# MindPX_V2_8_SCH.net
KiCad netlist of a schematic drawn in Altium Designer
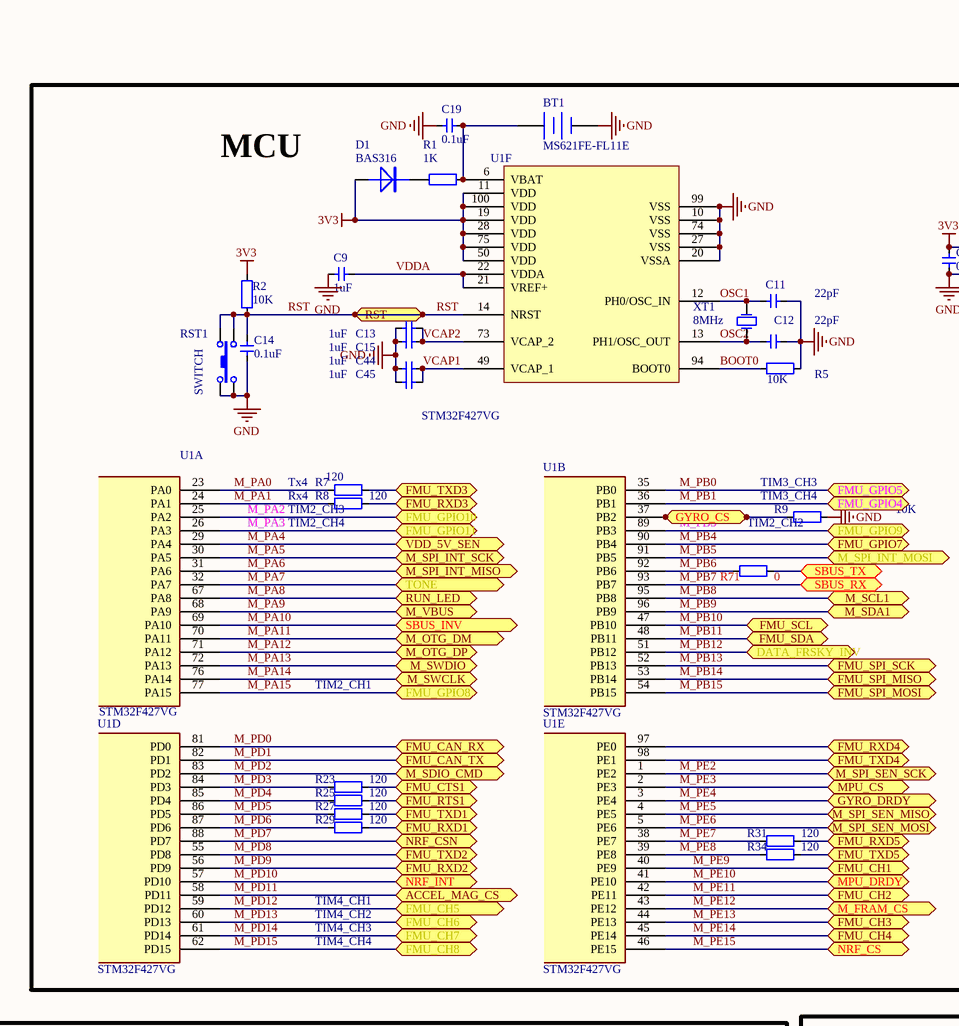
[diagram p0: MindPX V2.8 SCH.SchDoc, top left]
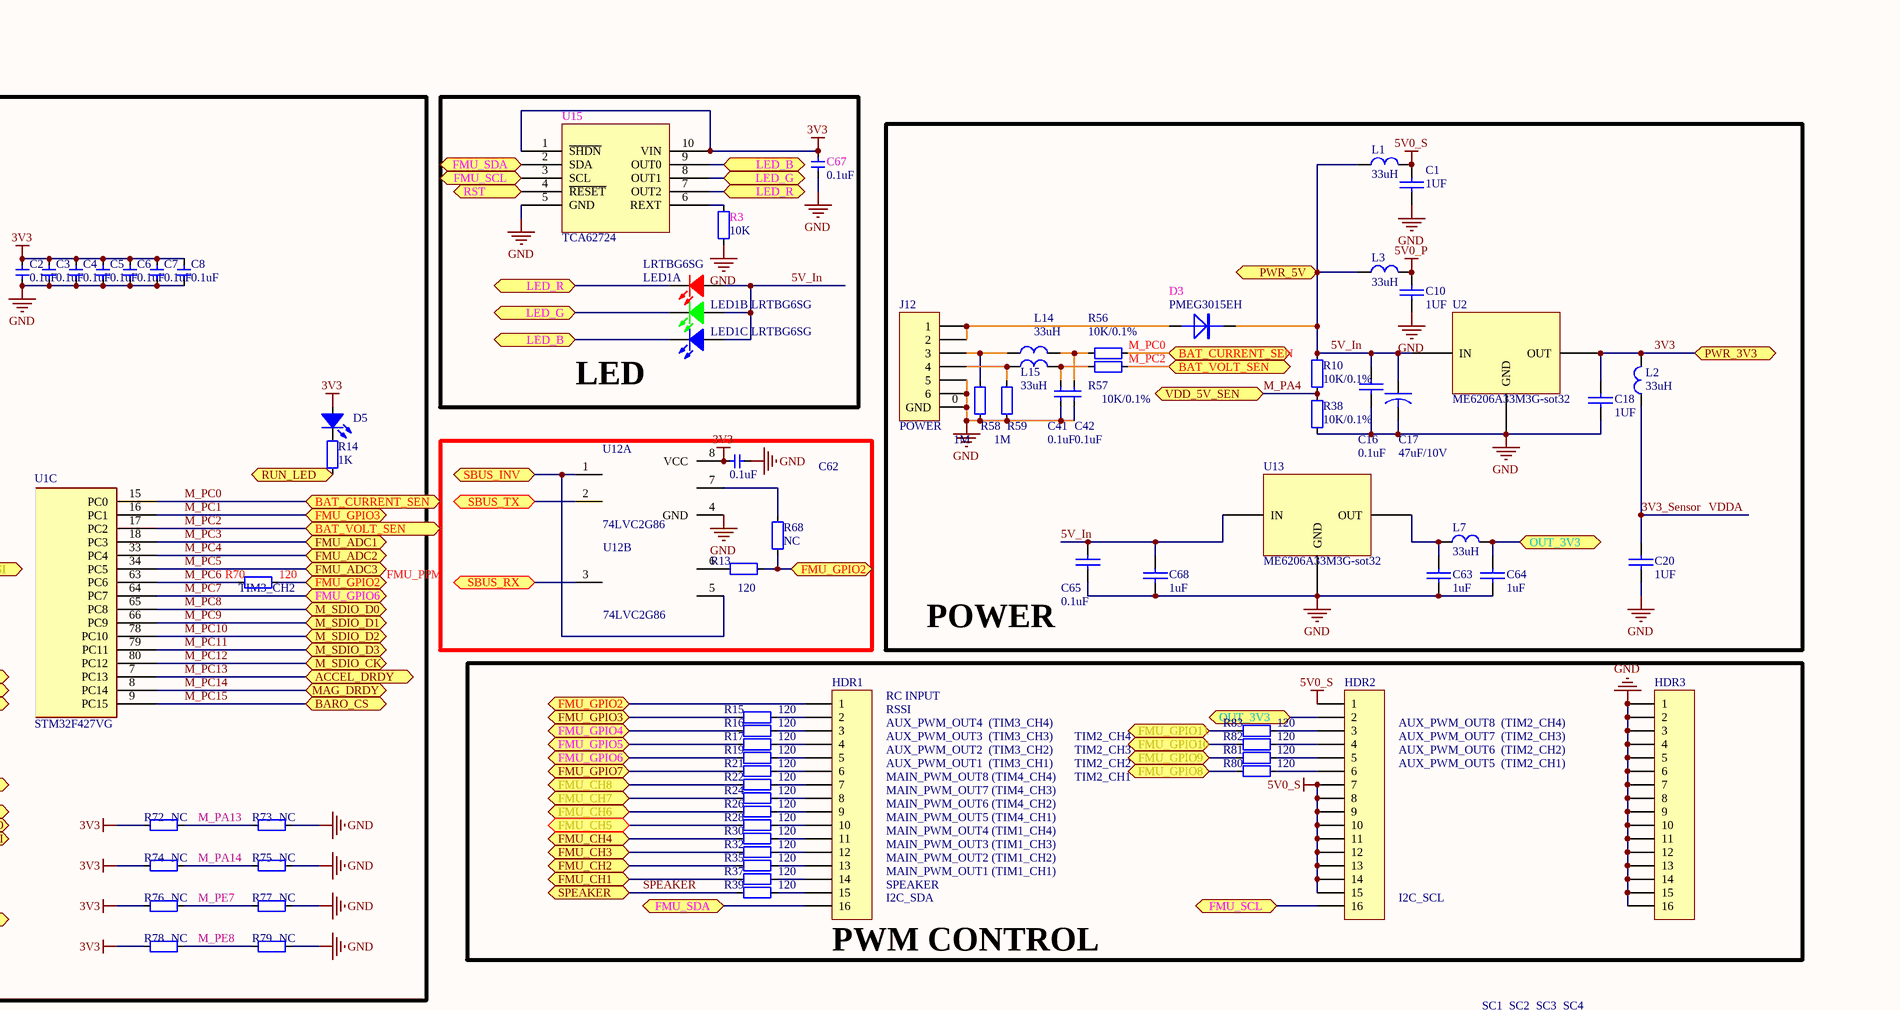
[diagram p1: MindPX V2.8 SCH.SchDoc, top right]
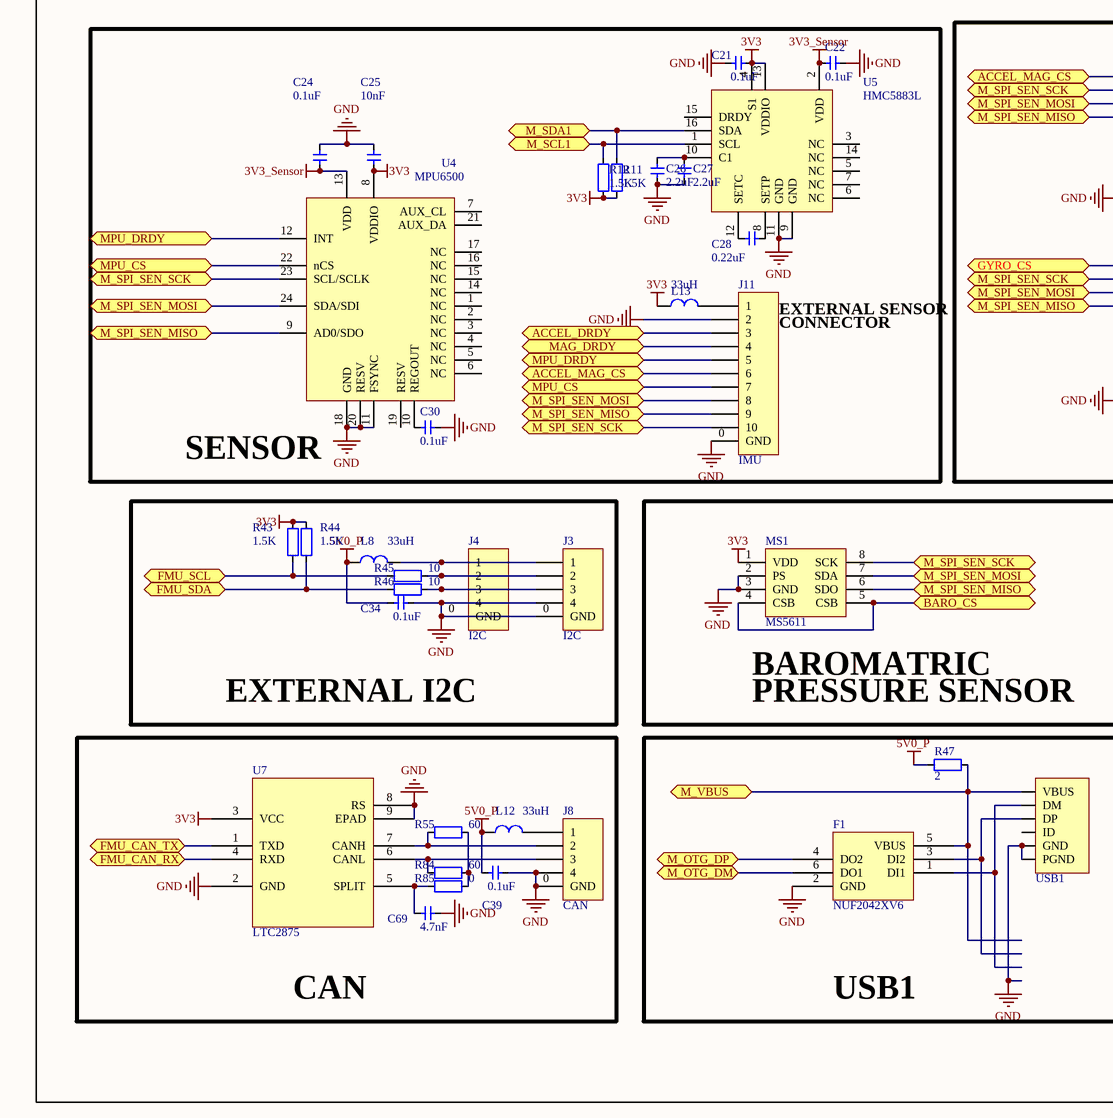
[diagram p2: MindPX V2.8 SCH.SchDoc, bottom left]
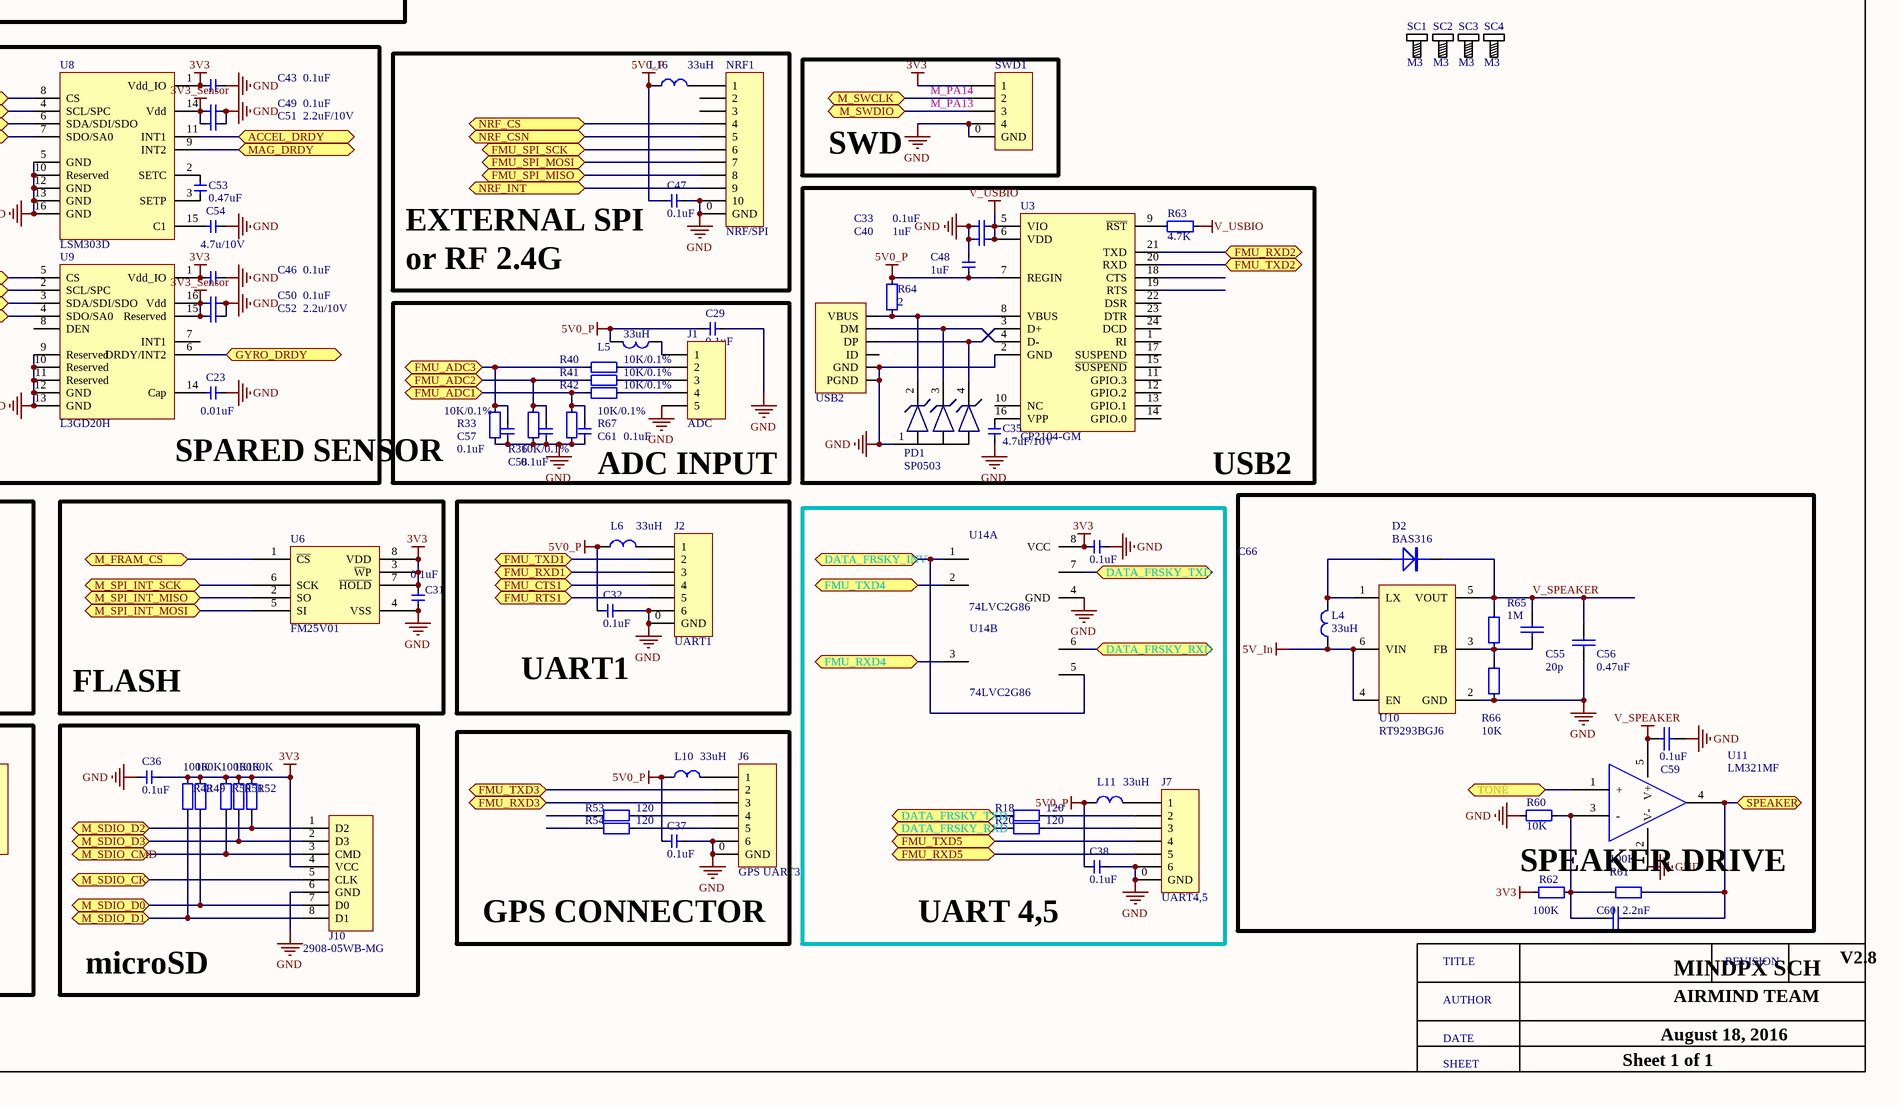
[diagram p3: MindPX V2.8 SCH.SchDoc, bottom right]

(export (version "E")
  (design (tool "Eeschema 10.0.6"))
  (components
    (comp (ref "BT1")
      (value "MS621FE-FL11E")
      (footprint "MS621FE")
      (description "Multicell Battery")
      (fields (field (name "PUBLISHER") "Altium Limited"))
      (libsource (lib "Miscellaneous Devices") (part "Battery"))
    )
    (comp (ref "C1")
      (value "1UF")
      (footprint "C0603")
      (description "Capacitor")
      (libsource (lib "*") (part "CAP"))
    )
    (comp (ref "C2")
      (value "0.1uF")
      (footprint "C0603")
      (description "Capacitor")
      (libsource (lib "SCH_Passive") (part "Cap_0603"))
    )
    (comp (ref "C3")
      (value "0.1uF")
      (footprint "C0603")
      (description "Capacitor")
      (libsource (lib "SCH_Passive") (part "Cap_0603"))
    )
    (comp (ref "C4")
      (value "0.1uF")
      (footprint "C0603")
      (description "Capacitor")
      (libsource (lib "SCH_Passive") (part "Cap_0603"))
    )
    (comp (ref "C5")
      (value "0.1uF")
      (footprint "C0603")
      (description "Capacitor")
      (libsource (lib "SCH_Passive") (part "Cap_0603"))
    )
    (comp (ref "C6")
      (value "0.1uF")
      (footprint "C0603")
      (description "Capacitor")
      (libsource (lib "SCH_Passive") (part "Cap_0603"))
    )
    (comp (ref "C7")
      (value "0.1uF")
      (footprint "C0603")
      (description "Capacitor")
      (libsource (lib "SCH_Passive") (part "Cap_0603"))
    )
    (comp (ref "C8")
      (value "0.1uF")
      (footprint "C0603")
      (description "Capacitor")
      (libsource (lib "SCH_Passive") (part "Cap_0603"))
    )
    (comp (ref "C9")
      (value "1uF")
      (footprint "C0603")
      (description "Capacitor")
      (libsource (lib "SCH_Passive") (part "Cap_0603"))
    )
    (comp (ref "C10")
      (value "1UF")
      (footprint "C0603")
      (description "Capacitor")
      (libsource (lib "*") (part "CAP"))
    )
    (comp (ref "C11")
      (value "22pF")
      (footprint "C0603")
      (description "Capacitor")
      (libsource (lib "SCH_Passive") (part "Cap_0603"))
    )
    (comp (ref "C12")
      (value "22pF")
      (footprint "C0603")
      (description "Capacitor")
      (libsource (lib "SCH_Passive") (part "Cap_0603"))
    )
    (comp (ref "C13")
      (value "1uF")
      (footprint "C0603")
      (description "Capacitor")
      (libsource (lib "SCH_Passive") (part "Cap_0603"))
    )
    (comp (ref "C14")
      (value "0.1uF")
      (footprint "C0603")
      (description "Capacitor")
      (libsource (lib "SCH_Passive") (part "Cap_0603"))
    )
    (comp (ref "C15")
      (value "1uF")
      (footprint "C0603")
      (description "Capacitor")
      (libsource (lib "SCH_Passive") (part "Cap_0603"))
    )
    (comp (ref "C16")
      (value "0.1uF")
      (footprint "C0603")
      (description "Capacitor")
      (libsource (lib "*") (part "CAP"))
    )
    (comp (ref "C17")
      (value "47uF/10V")
      (footprint "钽电容")
      (description "Capacitor")
      (libsource (lib "*") (part "CAPACITOR"))
    )
    (comp (ref "C18")
      (value "1UF")
      (footprint "C0603")
      (description "Capacitor")
      (libsource (lib "*") (part "CAP"))
    )
    (comp (ref "C19")
      (value "0.1uF")
      (footprint "C0603")
      (description "Capacitor")
      (libsource (lib "SCH_Passive") (part "Cap_0603"))
    )
    (comp (ref "C20")
      (value "1UF")
      (footprint "C0603")
      (description "Capacitor")
      (libsource (lib "*") (part "CAP"))
    )
    (comp (ref "C21")
      (value "0.1uF")
      (footprint "C0603")
      (description "Capacitor")
      (libsource (lib "SCH_Passive") (part "Cap_0603"))
    )
    (comp (ref "C22")
      (value "0.1uF")
      (footprint "C0603")
      (description "Capacitor")
      (libsource (lib "SCH_Passive") (part "Cap_0603"))
    )
    (comp (ref "C23")
      (value "0.01uF")
      (footprint "C0603")
      (description "Capacitor")
      (libsource (lib "SCH_Passive") (part "Cap_0603"))
    )
    (comp (ref "C24")
      (value "0.1uF")
      (footprint "C0603")
      (description "Capacitor")
      (libsource (lib "SCH_Passive") (part "Cap_0603"))
    )
    (comp (ref "C25")
      (value "10nF")
      (footprint "C0603")
      (description "Capacitor")
      (libsource (lib "SCH_Passive") (part "Cap_0603"))
    )
    (comp (ref "C26")
      (value "2.2uF")
      (footprint "C0603")
      (description "Capacitor")
      (libsource (lib "SCH_Passive") (part "Cap_0603"))
    )
    (comp (ref "C27")
      (value "2.2uF")
      (footprint "C0603")
      (description "Capacitor")
      (libsource (lib "SCH_Passive") (part "Cap_0603"))
    )
    (comp (ref "C28")
      (value "0.22uF")
      (footprint "C0603")
      (description "Capacitor")
      (libsource (lib "SCH_Passive") (part "Cap_0603"))
    )
    (comp (ref "C29")
      (value "0.1uF")
      (footprint "C0603")
      (description "Capacitor")
      (libsource (lib "SCH_Passive") (part "Cap_0603"))
    )
    (comp (ref "C30")
      (value "0.1uF")
      (footprint "C0603")
      (description "Capacitor")
      (libsource (lib "SCH_Passive") (part "Cap_0603"))
    )
    (comp (ref "C31")
      (value "0.1uF")
      (footprint "C0603")
      (description "Capacitor")
      (libsource (lib "SCH_Passive") (part "Cap_0603"))
    )
    (comp (ref "C32")
      (value "0.1uF")
      (footprint "C0603")
      (description "Capacitor")
      (libsource (lib "SCH_Passive") (part "Cap_0603"))
    )
    (comp (ref "C33")
      (value "0.1uF")
      (footprint "C0603")
      (description "Capacitor")
      (libsource (lib "SCH_Passive") (part "Cap_0603"))
    )
    (comp (ref "C34")
      (value "0.1uF")
      (footprint "C0603")
      (description "Capacitor")
      (libsource (lib "SCH_Passive") (part "Cap_0603"))
    )
    (comp (ref "C35")
      (value "4.7uF/10V")
      (footprint "C0603")
      (description "Capacitor")
      (libsource (lib "SCH_Passive") (part "Cap_0603"))
    )
    (comp (ref "C36")
      (value "0.1uF")
      (footprint "C0603")
      (description "Capacitor")
      (libsource (lib "SCH_Passive") (part "Cap_0603"))
    )
    (comp (ref "C37")
      (value "0.1uF")
      (footprint "C0603")
      (description "Capacitor")
      (libsource (lib "SCH_Passive") (part "Cap_0603"))
    )
    (comp (ref "C38")
      (value "0.1uF")
      (footprint "C0603")
      (description "Capacitor")
      (libsource (lib "SCH_Passive") (part "Cap_0603"))
    )
    (comp (ref "C39")
      (value "0.1uF")
      (footprint "C0603")
      (description "Capacitor")
      (libsource (lib "SCH_Passive") (part "Cap_0603"))
    )
    (comp (ref "C40")
      (value "1uF")
      (footprint "C0603")
      (description "Capacitor")
      (libsource (lib "SCH_Passive") (part "Cap_0603"))
    )
    (comp (ref "C41")
      (value "0.1uF")
      (footprint "C0603")
      (description "Capacitor")
      (libsource (lib "") (part "Cap_0603_1"))
    )
    (comp (ref "C42")
      (value "0.1uF")
      (footprint "C0603")
      (description "Capacitor")
      (libsource (lib "") (part "Cap_0603_1"))
    )
    (comp (ref "C43")
      (value "0.1uF")
      (footprint "C0603")
      (description "Capacitor")
      (libsource (lib "SCH_Passive") (part "Cap_0603"))
    )
    (comp (ref "C44")
      (value "1uF")
      (footprint "C0603")
      (description "Capacitor")
      (libsource (lib "SCH_Passive") (part "Cap_0603"))
    )
    (comp (ref "C45")
      (value "1uF")
      (footprint "C0603")
      (description "Capacitor")
      (libsource (lib "SCH_Passive") (part "Cap_0603"))
    )
    (comp (ref "C46")
      (value "0.1uF")
      (footprint "C0603")
      (description "Capacitor")
      (libsource (lib "SCH_Passive") (part "Cap_0603"))
    )
    (comp (ref "C47")
      (value "0.1uF")
      (footprint "C0603")
      (description "Capacitor")
      (libsource (lib "SCH_Passive") (part "Cap_0603"))
    )
    (comp (ref "C48")
      (value "1uF")
      (footprint "C0603")
      (description "Capacitor")
      (libsource (lib "SCH_Passive") (part "Cap_0603"))
    )
    (comp (ref "C49")
      (value "0.1uF")
      (footprint "C0603")
      (description "Capacitor")
      (libsource (lib "SCH_Passive") (part "Cap_0603"))
    )
    (comp (ref "C50")
      (value "0.1uF")
      (footprint "C0603")
      (description "Capacitor")
      (libsource (lib "SCH_Passive") (part "Cap_0603"))
    )
    (comp (ref "C51")
      (value "2.2uF/10V")
      (footprint "C0603")
      (description "Capacitor")
      (libsource (lib "SCH_Passive") (part "Cap_0603"))
    )
    (comp (ref "C52")
      (value "2.2u/10V")
      (footprint "C0603")
      (description "Capacitor")
      (libsource (lib "SCH_Passive") (part "Cap_0603"))
    )
    (comp (ref "C53")
      (value "0.47uF")
      (footprint "C0603")
      (description "Capacitor")
      (libsource (lib "SCH_Passive") (part "Cap_0603"))
    )
    (comp (ref "C54")
      (value "4.7u/10V")
      (footprint "C0603")
      (description "Capacitor")
      (libsource (lib "SCH_Passive") (part "Cap_0603"))
    )
    (comp (ref "C55")
      (value "20p")
      (footprint "C0603")
      (description "Capacitor")
      (libsource (lib "*") (part "CAP"))
    )
    (comp (ref "C56")
      (value "0.47uF")
      (footprint "C0805")
      (description "Capacitor")
      (libsource (lib "*") (part "CAP"))
    )
    (comp (ref "C57")
      (value "0.1uF")
      (footprint "C0603")
      (description "Capacitor")
      (libsource (lib "SCH_Passive") (part "Cap_0603"))
    )
    (comp (ref "C58")
      (value "0.1uF")
      (footprint "C0603")
      (description "Capacitor")
      (libsource (lib "SCH_Passive") (part "Cap_0603"))
    )
    (comp (ref "C59")
      (value "0.1uF")
      (footprint "C0603")
      (description "Capacitor")
      (libsource (lib "*") (part "CAP"))
    )
    (comp (ref "C60")
      (value "2.2nF")
      (footprint "C0603")
      (description "Capacitor")
      (libsource (lib "*") (part "CAP"))
    )
    (comp (ref "C61")
      (value "0.1uF")
      (footprint "C0603")
      (description "Capacitor")
      (libsource (lib "SCH_Passive") (part "Cap_0603"))
    )
    (comp (ref "C62")
      (value "0.1uF")
      (footprint "C0603")
      (description "Capacitor")
      (libsource (lib "SCH_Passive") (part "Cap_0603"))
    )
    (comp (ref "C63")
      (value "1uF")
      (footprint "C0603")
      (description "Capacitor")
      (libsource (lib "*") (part "CAP"))
    )
    (comp (ref "C64")
      (value "1uF")
      (footprint "C0603")
      (description "Capacitor")
      (libsource (lib "*") (part "CAP"))
    )
    (comp (ref "C65")
      (value "0.1uF")
      (footprint "C0603")
      (description "Capacitor")
      (libsource (lib "*") (part "CAP"))
    )
    (comp (ref "C66")
      (value "0.1uF")
      (footprint "C0603")
      (description "Capacitor")
      (libsource (lib "SCH_Passive") (part "Cap_0603"))
    )
    (comp (ref "C67")
      (value "0.1uF")
      (footprint "C0603")
      (description "Capacitor")
      (libsource (lib "") (part "Cap_0603_1"))
    )
    (comp (ref "C68")
      (value "1uF")
      (footprint "C0603")
      (description "Capacitor")
      (libsource (lib "*") (part "CAP"))
    )
    (comp (ref "C69")
      (value "4.7nF")
      (footprint "C0603")
      (description "Capacitor")
      (libsource (lib "SCH_Passive") (part "Cap_0603"))
    )
    (comp (ref "D1") (value "BAS316") (footprint "SOD323_AK") (libsource (lib "Zzhsch") (part "DIODE")))
    (comp (ref "D2") (value "BAS316") (footprint "SOD323_AK") (libsource (lib "Zzhsch") (part "DIODE")))
    (comp (ref "D3") (value "PMEG3015EH") (footprint "SOD123/X.85") (libsource (lib "Zzhsch") (part "DIODE")))
    (comp (ref "D5")
      (value "LED_0603")
      (footprint "0603")
      (description "LED")
      (libsource (lib "Zzhsch") (part "LED_0603"))
    )
    (comp (ref "F1")
      (value "NUF2042XV6")
      (footprint "SOT-563-6")
      (libsource (lib "Zzhsch") (part "NUF2042XV6"))
    )
    (comp (ref "HDR1")
      (value "MHDR1X16")
      (footprint "HDR1X16")
      (description "Header, 16-Pin")
      (fields (field (name "PUBLISHER") "Altium Limited"))
      (libsource (lib "Miscellaneous Connectors") (part "MHDR1X16"))
    )
    (comp (ref "HDR2")
      (value "MHDR1X16")
      (footprint "HDR1X16")
      (description "Header, 16-Pin")
      (fields (field (name "PUBLISHER") "Altium Limited"))
      (libsource (lib "Miscellaneous Connectors") (part "MHDR1X16"))
    )
    (comp (ref "HDR3")
      (value "MHDR1X16")
      (footprint "HDR1X16")
      (description "Header, 16-Pin")
      (fields (field (name "PUBLISHER") "Altium Limited"))
      (libsource (lib "Miscellaneous Connectors") (part "MHDR1X16"))
    )
    (comp (ref "J1")
      (value "ADC")
      (footprint "HDR1X5")
      (description "Header, 5-Pin")
      (fields (field (name "PUBLISHER") "Altium Limited"))
      (libsource (lib "Miscellaneous Connectors") (part "Header 5"))
    )
    (comp (ref "J2")
      (value "UART1")
      (footprint "DF13A-6P-1.25H")
      (description "Header, 7-Pin")
      (fields (field (name "PUBLISHER") "Altium Limited"))
      (libsource (lib "Zzhsch") (part "DF13_6"))
    )
    (comp (ref "J3")
      (value "I2C")
      (footprint "DF13A-4P-1.25H")
      (description "Header,4-Pin")
      (fields (field (name "PUBLISHER") "Altium Limited"))
      (libsource (lib "Zzhsch") (part "DF13_4"))
    )
    (comp (ref "J4")
      (value "I2C")
      (footprint "DF13A-4P-1.25H")
      (description "Header,4-Pin")
      (fields (field (name "PUBLISHER") "Altium Limited"))
      (libsource (lib "Zzhsch") (part "DF13_4"))
    )
    (comp (ref "J6")
      (value "GPS UART3")
      (footprint "DF13A-6P-1.25H")
      (description "Header, 7-Pin")
      (fields (field (name "PUBLISHER") "Altium Limited"))
      (libsource (lib "Zzhsch") (part "DF13_6"))
    )
    (comp (ref "J7")
      (value "UART4,5")
      (footprint "DF13A-6P-1.25H")
      (description "Header, 7-Pin")
      (fields (field (name "PUBLISHER") "Altium Limited"))
      (libsource (lib "Zzhsch") (part "DF13_6"))
    )
    (comp (ref "J8")
      (value "CAN")
      (footprint "DF13A-4P-1.25H")
      (description "Header,4-Pin")
      (fields (field (name "PUBLISHER") "Altium Limited"))
      (libsource (lib "Zzhsch") (part "DF13_4"))
    )
    (comp (ref "J10")
      (value "2908-05WB-MG")
      (footprint "SD_Card_TF")
      (description "SD")
      (libsource (lib "Zzhsch") (part "microSD_interface"))
    )
    (comp (ref "J11")
      (value "IMU")
      (footprint "FPC10/0.5")
      (description "Header, 8-Pin")
      (fields (field (name "PUBLISHER") "Altium Limited"))
      (libsource (lib "Zzhsch") (part "DF13_10"))
    )
    (comp (ref "J12")
      (value "POWER")
      (footprint "DF13A-6P-1.25H")
      (description "Header, 7-Pin")
      (fields (field (name "PUBLISHER") "Altium Limited"))
      (libsource (lib "") (part "DF13_6_1"))
    )
    (comp (ref "L1")
      (value "33uH")
      (footprint "L0603")
      (description "Inductor")
      (fields (field (name "PUBLISHER") "Altium Limited"))
      (libsource (lib "Zzhsch") (part "Inductor_smt"))
    )
    (comp (ref "L2")
      (value "33uH")
      (footprint "L0603")
      (description "Inductor")
      (fields (field (name "PUBLISHER") "Altium Limited"))
      (libsource (lib "Zzhsch") (part "Inductor_smt"))
    )
    (comp (ref "L3")
      (value "33uH")
      (footprint "L0603")
      (description "Inductor")
      (fields (field (name "PUBLISHER") "Altium Limited"))
      (libsource (lib "Zzhsch") (part "Inductor_smt"))
    )
    (comp (ref "L4")
      (value "33uH")
      (footprint "L0805")
      (description "Inductor")
      (fields (field (name "PUBLISHER") "Altium Limited"))
      (libsource (lib "Zzhsch") (part "Inductor_smt"))
    )
    (comp (ref "L5")
      (value "33uH")
      (footprint "L0603")
      (description "Inductor")
      (fields (field (name "PUBLISHER") "Altium Limited"))
      (libsource (lib "Zzhsch") (part "Inductor_smt"))
    )
    (comp (ref "L6")
      (value "33uH")
      (footprint "L0603")
      (description "Inductor")
      (fields (field (name "PUBLISHER") "Altium Limited"))
      (libsource (lib "Zzhsch") (part "Inductor_smt"))
    )
    (comp (ref "L7")
      (value "33uH")
      (footprint "L0603")
      (description "Inductor")
      (fields (field (name "PUBLISHER") "Altium Limited"))
      (libsource (lib "Zzhsch") (part "Inductor_smt"))
    )
    (comp (ref "L8")
      (value "33uH")
      (footprint "L0603")
      (description "Inductor")
      (fields (field (name "PUBLISHER") "Altium Limited"))
      (libsource (lib "Zzhsch") (part "Inductor_smt"))
    )
    (comp (ref "L10")
      (value "33uH")
      (footprint "L0603")
      (description "Inductor")
      (fields (field (name "PUBLISHER") "Altium Limited"))
      (libsource (lib "Zzhsch") (part "Inductor_smt"))
    )
    (comp (ref "L11")
      (value "33uH")
      (footprint "L0603")
      (description "Inductor")
      (fields (field (name "PUBLISHER") "Altium Limited"))
      (libsource (lib "Zzhsch") (part "Inductor_smt"))
    )
    (comp (ref "L12")
      (value "33uH")
      (footprint "L0603")
      (description "Inductor")
      (fields (field (name "PUBLISHER") "Altium Limited"))
      (libsource (lib "Zzhsch") (part "Inductor_smt"))
    )
    (comp (ref "L13")
      (value "33uH")
      (footprint "L0603")
      (description "Inductor")
      (fields (field (name "PUBLISHER") "Altium Limited"))
      (libsource (lib "Zzhsch") (part "Inductor_smt"))
    )
    (comp (ref "L14")
      (value "33uH")
      (footprint "L0603")
      (description "Inductor")
      (fields (field (name "PUBLISHER") "Altium Limited"))
      (libsource (lib "") (part "Inductor_smt_1"))
    )
    (comp (ref "L15")
      (value "33uH")
      (footprint "L0603")
      (description "Inductor")
      (fields (field (name "PUBLISHER") "Altium Limited"))
      (libsource (lib "") (part "Inductor_smt_1"))
    )
    (comp (ref "L16")
      (value "33uH")
      (footprint "L0603")
      (description "Inductor")
      (fields (field (name "PUBLISHER") "Altium Limited"))
      (libsource (lib "Zzhsch") (part "Inductor_smt"))
    )
    (comp (ref "LED1") (value "LRTBG6SG") (footprint "LRTBG6SG") (libsource (lib "Zzhsch") (part "LRTBG6SG")))
    (comp (ref "MS1")
      (value "MS5611")
      (footprint "MS5611")
      (description "Sensor")
      (libsource (lib "SCH_IC") (part "MS5611"))
    )
    (comp (ref "NRF1")
      (value "NRF/SPI")
      (footprint "DF13A-10P-1.25H")
      (description "Header, 8-Pin")
      (fields (field (name "PUBLISHER") "Altium Limited"))
      (libsource (lib "Zzhsch") (part "DF13_10"))
    )
    (comp (ref "PD1") (value "SP0503") (libsource (lib "Zzhsch") (part "SP0503")))
    (comp (ref "R1")
      (value "1K")
      (footprint "R0603")
      (description "Resistor")
      (libsource (lib "SCH_Passive") (part "Res_0603"))
    )
    (comp (ref "R2")
      (value "10K")
      (footprint "R0603")
      (description "Resistor")
      (libsource (lib "") (part "Res_0603_3"))
    )
    (comp (ref "R3")
      (value "10K")
      (footprint "R0603")
      (description "Resistor")
      (libsource (lib "") (part "Res_0603_1"))
    )
    (comp (ref "R5")
      (value "10K")
      (footprint "R0603")
      (description "Resistor")
      (libsource (lib "SCH_Passive") (part "Res_0603"))
    )
    (comp (ref "R7")
      (value "120")
      (footprint "R0603")
      (description "Resistor")
      (libsource (lib "SCH_Passive") (part "Res_0603"))
    )
    (comp (ref "R8")
      (value "120")
      (footprint "R0603")
      (description "Resistor")
      (libsource (lib "SCH_Passive") (part "Res_0603"))
    )
    (comp (ref "R9")
      (value "10K")
      (footprint "R0603")
      (description "Resistor")
      (libsource (lib "SCH_Passive") (part "Res_0603"))
    )
    (comp (ref "R10")
      (value "10K/0.1%")
      (footprint "R0603")
      (description "Resistor")
      (libsource (lib "") (part "Res_0603_1"))
    )
    (comp (ref "R11")
      (value "1.5K")
      (footprint "R0603")
      (description "Resistor")
      (libsource (lib "") (part "Res_0603_1"))
    )
    (comp (ref "R12")
      (value "1.5K")
      (footprint "R0603")
      (description "Resistor")
      (libsource (lib "") (part "Res_0603_3"))
    )
    (comp (ref "R13")
      (value "120")
      (footprint "R0603")
      (description "Resistor")
      (libsource (lib "SCH_Passive") (part "Res_0603"))
    )
    (comp (ref "R14")
      (value "1K")
      (footprint "R0603")
      (description "Resistor")
      (libsource (lib "") (part "Res_0603_3"))
    )
    (comp (ref "R15")
      (value "120")
      (footprint "R0603")
      (description "Resistor")
      (libsource (lib "SCH_Passive") (part "Res_0603"))
    )
    (comp (ref "R16")
      (value "120")
      (footprint "R0603")
      (description "Resistor")
      (libsource (lib "SCH_Passive") (part "Res_0603"))
    )
    (comp (ref "R17")
      (value "120")
      (footprint "R0603")
      (description "Resistor")
      (libsource (lib "SCH_Passive") (part "Res_0603"))
    )
    (comp (ref "R18")
      (value "120")
      (footprint "R0603")
      (description "Resistor")
      (libsource (lib "SCH_Passive") (part "Res_0603"))
    )
    (comp (ref "R19")
      (value "120")
      (footprint "R0603")
      (description "Resistor")
      (libsource (lib "SCH_Passive") (part "Res_0603"))
    )
    (comp (ref "R20")
      (value "120")
      (footprint "R0603")
      (description "Resistor")
      (libsource (lib "SCH_Passive") (part "Res_0603"))
    )
    (comp (ref "R21")
      (value "120")
      (footprint "R0603")
      (description "Resistor")
      (libsource (lib "SCH_Passive") (part "Res_0603"))
    )
    (comp (ref "R22")
      (value "120")
      (footprint "R0603")
      (description "Resistor")
      (libsource (lib "SCH_Passive") (part "Res_0603"))
    )
    (comp (ref "R23")
      (value "120")
      (footprint "R0603")
      (description "Resistor")
      (libsource (lib "SCH_Passive") (part "Res_0603"))
    )
    (comp (ref "R24")
      (value "120")
      (footprint "R0603")
      (description "Resistor")
      (libsource (lib "SCH_Passive") (part "Res_0603"))
    )
    (comp (ref "R25")
      (value "120")
      (footprint "R0603")
      (description "Resistor")
      (libsource (lib "SCH_Passive") (part "Res_0603"))
    )
    (comp (ref "R26")
      (value "120")
      (footprint "R0603")
      (description "Resistor")
      (libsource (lib "SCH_Passive") (part "Res_0603"))
    )
    (comp (ref "R27")
      (value "120")
      (footprint "R0603")
      (description "Resistor")
      (libsource (lib "SCH_Passive") (part "Res_0603"))
    )
    (comp (ref "R28")
      (value "120")
      (footprint "R0603")
      (description "Resistor")
      (libsource (lib "SCH_Passive") (part "Res_0603"))
    )
    (comp (ref "R29")
      (value "120")
      (footprint "R0603")
      (description "Resistor")
      (libsource (lib "SCH_Passive") (part "Res_0603"))
    )
    (comp (ref "R30")
      (value "120")
      (footprint "R0603")
      (description "Resistor")
      (libsource (lib "SCH_Passive") (part "Res_0603"))
    )
    (comp (ref "R31")
      (value "120")
      (footprint "R0603")
      (description "Resistor")
      (libsource (lib "SCH_Passive") (part "Res_0603"))
    )
    (comp (ref "R32")
      (value "120")
      (footprint "R0603")
      (description "Resistor")
      (libsource (lib "SCH_Passive") (part "Res_0603"))
    )
    (comp (ref "R33")
      (value "10K/0.1%")
      (footprint "R0603")
      (description "Resistor")
      (libsource (lib "") (part "Res_0603_1"))
    )
    (comp (ref "R34")
      (value "120")
      (footprint "R0603")
      (description "Resistor")
      (libsource (lib "SCH_Passive") (part "Res_0603"))
    )
    (comp (ref "R35")
      (value "120")
      (footprint "R0603")
      (description "Resistor")
      (libsource (lib "SCH_Passive") (part "Res_0603"))
    )
    (comp (ref "R36")
      (value "10K/0.1%")
      (footprint "R0603")
      (description "Resistor")
      (libsource (lib "") (part "Res_0603_1"))
    )
    (comp (ref "R37")
      (value "120")
      (footprint "R0603")
      (description "Resistor")
      (libsource (lib "SCH_Passive") (part "Res_0603"))
    )
    (comp (ref "R38")
      (value "10K/0.1%")
      (footprint "R0603")
      (description "Resistor")
      (libsource (lib "") (part "Res_0603_1"))
    )
    (comp (ref "R39")
      (value "120")
      (footprint "R0603")
      (description "Resistor")
      (libsource (lib "SCH_Passive") (part "Res_0603"))
    )
    (comp (ref "R40")
      (value "10K/0.1%")
      (footprint "R0603")
      (description "Resistor")
      (libsource (lib "SCH_Passive") (part "Res_0603"))
    )
    (comp (ref "R41")
      (value "10K/0.1%")
      (footprint "R0603")
      (description "Resistor")
      (libsource (lib "SCH_Passive") (part "Res_0603"))
    )
    (comp (ref "R42")
      (value "10K/0.1%")
      (footprint "R0603")
      (description "Resistor")
      (libsource (lib "SCH_Passive") (part "Res_0603"))
    )
    (comp (ref "R43")
      (value "1.5K")
      (footprint "R0603")
      (description "Resistor")
      (libsource (lib "") (part "Res_0603_1"))
    )
    (comp (ref "R44")
      (value "1.5K")
      (footprint "R0603")
      (description "Resistor")
      (libsource (lib "") (part "Res_0603_1"))
    )
    (comp (ref "R45")
      (value "10")
      (footprint "R0603")
      (description "Resistor")
      (libsource (lib "SCH_Passive") (part "Res_0603"))
    )
    (comp (ref "R46")
      (value "10")
      (footprint "R0603")
      (description "Resistor")
      (libsource (lib "SCH_Passive") (part "Res_0603"))
    )
    (comp (ref "R47")
      (value "2")
      (footprint "R0603")
      (description "Resistor")
      (libsource (lib "") (part "Res_0603_4"))
    )
    (comp (ref "R48")
      (value "100K")
      (footprint "R0603")
      (description "Resistor")
      (libsource (lib "") (part "Res_0603_1"))
    )
    (comp (ref "R49")
      (value "100K")
      (footprint "R0603")
      (description "Resistor")
      (libsource (lib "") (part "Res_0603_1"))
    )
    (comp (ref "R50")
      (value "100K")
      (footprint "R0603")
      (description "Resistor")
      (libsource (lib "") (part "Res_0603_1"))
    )
    (comp (ref "R51")
      (value "100K")
      (footprint "R0603")
      (description "Resistor")
      (libsource (lib "") (part "Res_0603_1"))
    )
    (comp (ref "R52")
      (value "100K")
      (footprint "R0603")
      (description "Resistor")
      (libsource (lib "") (part "Res_0603_1"))
    )
    (comp (ref "R53")
      (value "120")
      (footprint "R0603")
      (description "Resistor")
      (libsource (lib "SCH_Passive") (part "Res_0603"))
    )
    (comp (ref "R54")
      (value "120")
      (footprint "R0603")
      (description "Resistor")
      (libsource (lib "SCH_Passive") (part "Res_0603"))
    )
    (comp (ref "R55")
      (value "60")
      (footprint "R0603")
      (description "Resistor")
      (libsource (lib "SCH_Passive") (part "Res_0603"))
    )
    (comp (ref "R56")
      (value "10K/0.1%")
      (footprint "R0603")
      (description "Resistor")
      (libsource (lib "SCH_Passive") (part "Res_0603"))
    )
    (comp (ref "R57")
      (value "10K/0.1%")
      (footprint "R0603")
      (description "Resistor")
      (libsource (lib "SCH_Passive") (part "Res_0603"))
    )
    (comp (ref "R58")
      (value "1M")
      (footprint "R0603")
      (description "Resistor")
      (libsource (lib "") (part "Res_0603_1"))
    )
    (comp (ref "R59")
      (value "1M")
      (footprint "R0603")
      (description "Resistor")
      (libsource (lib "") (part "Res_0603_1"))
    )
    (comp (ref "R60")
      (value "10K")
      (footprint "R0603")
      (description "Resistor")
      (libsource (lib "") (part "Res_0603_4"))
    )
    (comp (ref "R61")
      (value "100K")
      (footprint "R0603")
      (description "Resistor")
      (libsource (lib "") (part "Res_0603_4"))
    )
    (comp (ref "R62")
      (value "100K")
      (footprint "R0603")
      (description "Resistor")
      (libsource (lib "SCH_Passive") (part "Res_0603"))
    )
    (comp (ref "R63")
      (value "4.7K")
      (footprint "R0603")
      (description "Resistor")
      (libsource (lib "") (part "Res_0603_3"))
    )
    (comp (ref "R64")
      (value "2")
      (footprint "R0603")
      (description "Resistor")
      (libsource (lib "") (part "Res_0603_2"))
    )
    (comp (ref "R65")
      (value "1M")
      (footprint "R0603")
      (description "Resistor")
      (libsource (lib "") (part "Res_0603_1"))
    )
    (comp (ref "R66")
      (value "10K")
      (footprint "R0603")
      (description "Resistor")
      (libsource (lib "") (part "Res_0603_1"))
    )
    (comp (ref "R67")
      (value "10K/0.1%")
      (footprint "R0603")
      (description "Resistor")
      (libsource (lib "") (part "Res_0603_1"))
    )
    (comp (ref "R68")
      (value "NC")
      (footprint "R0603")
      (description "Resistor")
      (libsource (lib "") (part "Res_0603_1"))
    )
    (comp (ref "R70")
      (value "120")
      (footprint "R0603")
      (description "Resistor")
      (libsource (lib "SCH_Passive") (part "Res_0603"))
    )
    (comp (ref "R71")
      (value "0")
      (footprint "R0603")
      (description "Resistor")
      (libsource (lib "SCH_Passive") (part "Res_0603"))
    )
    (comp (ref "R72")
      (value "NC")
      (footprint "R0603")
      (description "Resistor")
      (libsource (lib "SCH_Passive") (part "Res_0603"))
    )
    (comp (ref "R73")
      (value "NC")
      (footprint "R0603")
      (description "Resistor")
      (libsource (lib "SCH_Passive") (part "Res_0603"))
    )
    (comp (ref "R74")
      (value "NC")
      (footprint "R0603")
      (description "Resistor")
      (libsource (lib "SCH_Passive") (part "Res_0603"))
    )
    (comp (ref "R75")
      (value "NC")
      (footprint "R0603")
      (description "Resistor")
      (libsource (lib "SCH_Passive") (part "Res_0603"))
    )
    (comp (ref "R76")
      (value "NC")
      (footprint "R0603")
      (description "Resistor")
      (libsource (lib "SCH_Passive") (part "Res_0603"))
    )
    (comp (ref "R77")
      (value "NC")
      (footprint "R0603")
      (description "Resistor")
      (libsource (lib "SCH_Passive") (part "Res_0603"))
    )
    (comp (ref "R78")
      (value "NC")
      (footprint "R0603")
      (description "Resistor")
      (libsource (lib "SCH_Passive") (part "Res_0603"))
    )
    (comp (ref "R79")
      (value "NC")
      (footprint "R0603")
      (description "Resistor")
      (libsource (lib "SCH_Passive") (part "Res_0603"))
    )
    (comp (ref "R80")
      (value "120")
      (footprint "R0603")
      (description "Resistor")
      (libsource (lib "SCH_Passive") (part "Res_0603"))
    )
    (comp (ref "R81")
      (value "120")
      (footprint "R0603")
      (description "Resistor")
      (libsource (lib "SCH_Passive") (part "Res_0603"))
    )
    (comp (ref "R82")
      (value "120")
      (footprint "R0603")
      (description "Resistor")
      (libsource (lib "SCH_Passive") (part "Res_0603"))
    )
    (comp (ref "R83")
      (value "120")
      (footprint "R0603")
      (description "Resistor")
      (libsource (lib "SCH_Passive") (part "Res_0603"))
    )
    (comp (ref "R84")
      (value "60")
      (footprint "R0603")
      (description "Resistor")
      (libsource (lib "SCH_Passive") (part "Res_0603"))
    )
    (comp (ref "R85")
      (value "0")
      (footprint "R0603")
      (description "Resistor")
      (libsource (lib "SCH_Passive") (part "Res_0603"))
    )
    (comp (ref "RST1")
      (value "SWITCH")
      (footprint "BT_TACT_3.5*3.55_90")
      (description "Switch")
      (libsource (lib "SCH_Switch") (part "BT_TACT_3.5*5_90"))
    )
    (comp (ref "SC1")
      (value "M3")
      (footprint "SCRREW_M3")
      (description "Screw")
      (libsource (lib "Zzhsch") (part "Screw_M3"))
    )
    (comp (ref "SC2")
      (value "M3")
      (footprint "SCRREW_M3")
      (description "Screw")
      (libsource (lib "Zzhsch") (part "Screw_M3"))
    )
    (comp (ref "SC3")
      (value "M3")
      (footprint "SCRREW_M3")
      (description "Screw")
      (libsource (lib "Zzhsch") (part "Screw_M3"))
    )
    (comp (ref "SC4")
      (value "M3")
      (footprint "SCRREW_M3")
      (description "Screw")
      (libsource (lib "Zzhsch") (part "Screw_M3"))
    )
    (comp (ref "SWD1")
      (value "DEBUG")
      (footprint "DF13A-4P-1.25H")
      (description "Header,4-Pin")
      (fields (field (name "PUBLISHER") "Altium Limited"))
      (libsource (lib "Zzhsch") (part "DF13_4"))
    )
    (comp (ref "U1")
      (value "STM32F427VG")
      (footprint "LQFP100")
      (libsource (lib "Zzhsch") (part "STM32F427VX"))
    )
    (comp (ref "U2")
      (value "ME6206A33M3G-sot32")
      (footprint "me6206a33mg-sot23")
      (libsource (lib "本地") (part "SOP-3"))
    )
    (comp (ref "U3") (value "CP2104-GM") (footprint "QFN24") (libsource (lib "Zzhsch") (part "CP2104")))
    (comp (ref "U4") (value "MPU6500") (footprint "MPU6500") (libsource (lib "Zzhsch") (part "MPU-6500")))
    (comp (ref "U5") (value "HMC5883L") (footprint "LPcc16") (libsource (lib "Zzhsch") (part "HMC5883L")))
    (comp (ref "U6") (value "FM25V01") (footprint "so8") (libsource (lib "Zzhsch") (part "FM25V01")))
    (comp (ref "U7")
      (value "LTC2875")
      (footprint "DFN-8_DD")
      (libsource (lib "Schlib-og-lib1") (part "LTC2875"))
    )
    (comp (ref "U8") (value "LSM303D") (footprint "LSM303D") (libsource (lib "Zzhsch") (part "LSM303D")))
    (comp (ref "U9") (value "L3GD20H") (footprint "L3GD20H") (libsource (lib "Zzhsch") (part "L3GD20H")))
    (comp (ref "U10")
      (value "RT9293BGJ6")
      (footprint "TSOT23-6")
      (description "注意要50V的，不要搞成20V的")
      (libsource (lib "Zzhsch") (part "RT9293"))
    )
    (comp (ref "U11") (value "LM321MF") (footprint "SOT23-5") (libsource (lib "Zzhsch") (part "LM321MF")))
    (comp (ref "U12") (value "74LVC2G86") (footprint "VSSOP8") (libsource (lib "Zzhsch") (part "74LVC2G86")))
    (comp (ref "U13")
      (value "ME6206A33M3G-sot32")
      (footprint "me6206a33mg-sot23")
      (libsource (lib "本地") (part "SOP-3"))
    )
    (comp (ref "U14") (value "74LVC2G86") (footprint "VSSOP8") (libsource (lib "Zzhsch") (part "74LVC2G86")))
    (comp (ref "U15")
      (value "TCA62724")
      (footprint "SON10")
      (libsource (lib "Schlib-og-lib1") (part "TCA62724"))
    )
    (comp (ref "USB1")
      (value "USB_QG")
      (footprint "MicroUSB_T2")
      (description "USB")
      (libsource (lib "Zzhsch") (part "USB_Micro"))
    )
    (comp (ref "USB2")
      (value "USB_Micro")
      (footprint "MicroUSB_T2")
      (description "USB")
      (libsource (lib "") (part "USB_Micro_1"))
    )
    (comp (ref "XT1")
      (value "8MHz")
      (footprint "XTAL_5032")
      (description "Crystal Oscillator")
      (fields (field (name "Comment") "XTAL_5032_2P"))
      (libsource (lib "SCH_Oscillator") (part "XTAL_5032_2P"))
    )
  )
  (nets
    (net (code "2") (name "/BOOT0") (class "Default")
      (node (ref "R5") (pin "2") (pinfunction "2_2") (pintype "passive"))
      (node (ref "U1") (pin "94") (pinfunction "BOOT0_94") (pintype "passive"))
    )
    (net (code "3") (name "/DATA_FRSKY_RXD") (class "Default")
      (node (ref "R20") (pin "2") (pinfunction "2_2") (pintype "passive"))
      (node (ref "U14") (pin "6") (pinfunction "2B_6") (pintype "passive"))
    )
    (net (code "4") (name "/DATA_FRSKY_TXD") (class "Default")
      (node (ref "R18") (pin "2") (pinfunction "2_2") (pintype "passive"))
      (node (ref "U14") (pin "7") (pinfunction "1Y_7") (pintype "passive"))
    )
    (net (code "5") (name "/FMU_CTS1") (class "Default")
      (node (ref "J2") (pin "4") (pinfunction "4_4") (pintype "passive"))
      (node (ref "R23") (pin "1") (pinfunction "1_1") (pintype "passive"))
    )
    (net (code "6") (name "/FMU_GPIO2") (class "Default")
      (node (ref "HDR1") (pin "1") (pinfunction "1_1") (pintype "passive"))
      (node (ref "R13") (pin "1") (pinfunction "1_1") (pintype "passive"))
      (node (ref "R68") (pin "2") (pinfunction "2_2") (pintype "passive"))
      (node (ref "R70") (pin "1") (pinfunction "1_1") (pintype "passive"))
    )
    (net (code "7") (name "/FMU_RTS1") (class "Default")
      (node (ref "J2") (pin "5") (pinfunction "5_5") (pintype "passive"))
      (node (ref "R25") (pin "1") (pinfunction "1_1") (pintype "passive"))
    )
    (net (code "8") (name "/FMU_RXD1") (class "Default")
      (node (ref "J2") (pin "3") (pinfunction "3_3") (pintype "passive"))
      (node (ref "R29") (pin "1") (pinfunction "1_1") (pintype "passive"))
    )
    (net (code "9") (name "/FMU_RXD3") (class "Default")
      (node (ref "J6") (pin "3") (pinfunction "3_3") (pintype "passive"))
      (node (ref "R8") (pin "1") (pinfunction "1_1") (pintype "passive"))
    )
    (net (code "10") (name "/FMU_RXD4") (class "Default")
      (node (ref "U1") (pin "97") (pinfunction "PE0_97") (pintype "passive"))
      (node (ref "U14") (pin "3") (pinfunction "2Y_3") (pintype "passive"))
    )
    (net (code "11") (name "/FMU_RXD5") (class "Default")
      (node (ref "J7") (pin "5") (pinfunction "5_5") (pintype "passive"))
      (node (ref "R31") (pin "1") (pinfunction "1_1") (pintype "passive"))
    )
    (net (code "12") (name "/FMU_TXD1") (class "Default")
      (node (ref "J2") (pin "2") (pinfunction "2_2") (pintype "passive"))
      (node (ref "R27") (pin "1") (pinfunction "1_1") (pintype "passive"))
    )
    (net (code "13") (name "/FMU_TXD3") (class "Default")
      (node (ref "J6") (pin "2") (pinfunction "2_2") (pintype "passive"))
      (node (ref "R7") (pin "1") (pinfunction "1_1") (pintype "passive"))
    )
    (net (code "14") (name "/FMU_TXD4") (class "Default")
      (node (ref "U1") (pin "98") (pinfunction "PE1_98") (pintype "passive"))
      (node (ref "U14") (pin "2") (pinfunction "1B_2") (pintype "passive"))
    )
    (net (code "15") (name "/FMU_TXD5") (class "Default")
      (node (ref "J7") (pin "4") (pinfunction "4_4") (pintype "passive"))
      (node (ref "R34") (pin "1") (pinfunction "1_1") (pintype "passive"))
    )
    (net (code "16") (name "/GYRO_CS") (class "Default")
      (node (ref "R9") (pin "2") (pinfunction "2_2") (pintype "passive"))
      (node (ref "U1") (pin "37") (pinfunction "PB2_37") (pintype "passive"))
      (node (ref "U9") (pin "5") (pinfunction "CS_5") (pintype "passive"))
    )
    (net (code "17") (name "/LED_B") (class "Default")
      (node (ref "LED1") (pin "C3") (pinfunction "C3_C3") (pintype "passive"))
      (node (ref "U15") (pin "9") (pinfunction "OUT0_9") (pintype "passive"))
    )
    (net (code "18") (name "/LED_G") (class "Default")
      (node (ref "LED1") (pin "C2") (pinfunction "C2_C2") (pintype "passive"))
      (node (ref "U15") (pin "8") (pinfunction "OUT1_8") (pintype "passive"))
    )
    (net (code "19") (name "/LED_R") (class "Default")
      (node (ref "LED1") (pin "C1") (pinfunction "C1_C1") (pintype "passive"))
      (node (ref "U15") (pin "7") (pinfunction "OUT2_7") (pintype "passive"))
    )
    (net (code "20") (name "/M_PA0") (class "Default")
      (node (ref "R7") (pin "2") (pinfunction "2_2") (pintype "passive"))
      (node (ref "U1") (pin "23") (pinfunction "PA0_23") (pintype "passive"))
    )
    (net (code "21") (name "/M_PA1") (class "Default")
      (node (ref "R8") (pin "2") (pinfunction "2_2") (pintype "passive"))
      (node (ref "U1") (pin "24") (pinfunction "PA1_24") (pintype "passive"))
    )
    (net (code "22") (name "/M_PA2") (class "Default")
      (node (ref "R82") (pin "2") (pinfunction "2_2") (pintype "passive"))
      (node (ref "U1") (pin "25") (pinfunction "PA2_25") (pintype "passive"))
    )
    (net (code "23") (name "/M_PA3") (class "Default")
      (node (ref "R83") (pin "2") (pinfunction "2_2") (pintype "passive"))
      (node (ref "U1") (pin "26") (pinfunction "PA3_26") (pintype "passive"))
    )
    (net (code "24") (name "/M_PA4") (class "Default")
      (node (ref "R10") (pin "2") (pinfunction "2_2") (pintype "passive"))
      (node (ref "R38") (pin "1") (pinfunction "1_1") (pintype "passive"))
      (node (ref "U1") (pin "29") (pinfunction "PA4_29") (pintype "passive"))
    )
    (net (code "25") (name "/M_PA5") (class "Default")
      (node (ref "U1") (pin "30") (pinfunction "PA5_30") (pintype "passive"))
      (node (ref "U6") (pin "6") (pinfunction "SCK_6") (pintype "passive"))
    )
    (net (code "26") (name "/M_PA6") (class "Default")
      (node (ref "U1") (pin "31") (pinfunction "PA6_31") (pintype "passive"))
      (node (ref "U6") (pin "2") (pinfunction "SO_2") (pintype "passive"))
    )
    (net (code "27") (name "/M_PA7") (class "Default")
      (node (ref "U1") (pin "32") (pinfunction "PA7_32") (pintype "passive"))
      (node (ref "U11") (pin "1") (pinfunction "+_1") (pintype "passive"))
    )
    (net (code "28") (name "/M_PA8") (class "Default")
      (node (ref "R14") (pin "1") (pinfunction "1_1") (pintype "passive"))
      (node (ref "U1") (pin "67") (pinfunction "PA8_67") (pintype "passive"))
    )
    (net (code "29") (name "/M_PA9") (class "Default")
      (node (ref "F1") (pin "5") (pinfunction "VBUS_5") (pintype "passive"))
      (node (ref "R47") (pin "2") (pinfunction "2_2") (pintype "passive"))
      (node (ref "U1") (pin "68") (pinfunction "PA9_68") (pintype "passive"))
      (node (ref "USB1") (pin "1") (pinfunction "VBUS_1") (pintype "passive"))
    )
    (net (code "30") (name "/M_PA10") (class "Default")
      (node (ref "U1") (pin "69") (pinfunction "PA10_69") (pintype "passive"))
      (node (ref "U12") (pin "1") (pinfunction "1A_1") (pintype "passive"))
      (node (ref "U12") (pin "5") (pinfunction "2A_5") (pintype "passive"))
    )
    (net (code "31") (name "/M_PA11") (class "Default")
      (node (ref "F1") (pin "6") (pinfunction "DO1_6") (pintype "passive"))
      (node (ref "U1") (pin "70") (pinfunction "PA11_70") (pintype "passive"))
    )
    (net (code "32") (name "/M_PA12") (class "Default")
      (node (ref "F1") (pin "4") (pinfunction "DO2_4") (pintype "passive"))
      (node (ref "U1") (pin "71") (pinfunction "PA12_71") (pintype "passive"))
    )
    (net (code "33") (name "/M_PA13") (class "Default")
      (node (ref "R72") (pin "1") (pinfunction "1_1") (pintype "passive"))
      (node (ref "R73") (pin "2") (pinfunction "2_2") (pintype "passive"))
      (node (ref "SWD1") (pin "3") (pinfunction "3_3") (pintype "passive"))
      (node (ref "U1") (pin "72") (pinfunction "PA13_72") (pintype "passive"))
    )
    (net (code "34") (name "/M_PA14") (class "Default")
      (node (ref "R74") (pin "1") (pinfunction "1_1") (pintype "passive"))
      (node (ref "R75") (pin "2") (pinfunction "2_2") (pintype "passive"))
      (node (ref "SWD1") (pin "2") (pinfunction "2_2") (pintype "passive"))
      (node (ref "U1") (pin "76") (pinfunction "PA14_76") (pintype "passive"))
    )
    (net (code "35") (name "/M_PA15") (class "Default")
      (node (ref "R80") (pin "2") (pinfunction "2_2") (pintype "passive"))
      (node (ref "U1") (pin "77") (pinfunction "PA15_77") (pintype "passive"))
    )
    (net (code "36") (name "/M_PB0") (class "Default")
      (node (ref "R17") (pin "2") (pinfunction "2_2") (pintype "passive"))
      (node (ref "U1") (pin "35") (pinfunction "PB0_35") (pintype "passive"))
    )
    (net (code "37") (name "/M_PB1") (class "Default")
      (node (ref "R16") (pin "2") (pinfunction "2_2") (pintype "passive"))
      (node (ref "U1") (pin "36") (pinfunction "PB1_36") (pintype "passive"))
    )
    (net (code "38") (name "/M_PB3") (class "Default")
      (node (ref "R81") (pin "2") (pinfunction "2_2") (pintype "passive"))
      (node (ref "U1") (pin "89") (pinfunction "PB3_89") (pintype "passive"))
    )
    (net (code "39") (name "/M_PB4") (class "Default")
      (node (ref "R21") (pin "2") (pinfunction "2_2") (pintype "passive"))
      (node (ref "U1") (pin "90") (pinfunction "PB4_90") (pintype "passive"))
    )
    (net (code "40") (name "/M_PB5") (class "Default")
      (node (ref "U1") (pin "91") (pinfunction "PB5_91") (pintype "passive"))
      (node (ref "U6") (pin "5") (pinfunction "SI_5") (pintype "passive"))
    )
    (net (code "41") (name "/M_PB6") (class "Default")
      (node (ref "R71") (pin "2") (pinfunction "2_2") (pintype "passive"))
      (node (ref "U1") (pin "92") (pinfunction "PB6_92") (pintype "passive"))
    )
    (net (code "42") (name "/M_PB7") (class "Default")
      (node (ref "U1") (pin "93") (pinfunction "PB7_93") (pintype "passive"))
      (node (ref "U12") (pin "3") (pinfunction "2Y_3") (pintype "passive"))
    )
    (net (code "43") (name "/M_PB8") (class "Default")
      (node (ref "R12") (pin "2") (pinfunction "2_2") (pintype "passive"))
      (node (ref "U1") (pin "95") (pinfunction "PB8_95") (pintype "passive"))
      (node (ref "U5") (pin "1") (pinfunction "SCL_1") (pintype "passive"))
    )
    (net (code "44") (name "/M_PB9") (class "Default")
      (node (ref "R11") (pin "1") (pinfunction "1_1") (pintype "passive"))
      (node (ref "U1") (pin "96") (pinfunction "PB9_96") (pintype "passive"))
      (node (ref "U5") (pin "16") (pinfunction "SDA_16") (pintype "passive"))
    )
    (net (code "45") (name "/M_PB10") (class "Default")
      (node (ref "HDR2") (pin "16") (pinfunction "16_16") (pintype "passive"))
      (node (ref "R43") (pin "2") (pinfunction "2_2") (pintype "passive"))
      (node (ref "R45") (pin "2") (pinfunction "2_2") (pintype "passive"))
      (node (ref "U1") (pin "47") (pinfunction "PB10_47") (pintype "passive"))
      (node (ref "U15") (pin "3") (pinfunction "SCL_3") (pintype "passive"))
    )
    (net (code "46") (name "/M_PB11") (class "Default")
      (node (ref "HDR1") (pin "16") (pinfunction "16_16") (pintype "passive"))
      (node (ref "R44") (pin "2") (pinfunction "2_2") (pintype "passive"))
      (node (ref "R46") (pin "2") (pinfunction "2_2") (pintype "passive"))
      (node (ref "U1") (pin "48") (pinfunction "PB11_48") (pintype "passive"))
      (node (ref "U15") (pin "2") (pinfunction "SDA_2") (pintype "passive"))
    )
    (net (code "47") (name "/M_PB12") (class "Default")
      (node (ref "U1") (pin "51") (pinfunction "PB12_51") (pintype "passive"))
      (node (ref "U14") (pin "1") (pinfunction "1A_1") (pintype "passive"))
      (node (ref "U14") (pin "5") (pinfunction "2A_5") (pintype "passive"))
    )
    (net (code "48") (name "/M_PB13") (class "Default")
      (node (ref "NRF1") (pin "6") (pinfunction "6_6") (pintype "passive"))
      (node (ref "U1") (pin "52") (pinfunction "PB13_52") (pintype "passive"))
    )
    (net (code "49") (name "/M_PB14") (class "Default")
      (node (ref "NRF1") (pin "8") (pinfunction "8_8") (pintype "passive"))
      (node (ref "U1") (pin "53") (pinfunction "PB14_53") (pintype "passive"))
    )
    (net (code "50") (name "/M_PB15") (class "Default")
      (node (ref "NRF1") (pin "7") (pinfunction "7_7") (pintype "passive"))
      (node (ref "U1") (pin "54") (pinfunction "PB15_54") (pintype "passive"))
    )
    (net (code "51") (name "/M_PC0") (class "Default")
      (node (ref "R56") (pin "1") (pinfunction "1_1") (pintype "passive"))
      (node (ref "U1") (pin "15") (pinfunction "PC0_15") (pintype "passive"))
    )
    (net (code "52") (name "/M_PC1") (class "Default")
      (node (ref "R15") (pin "2") (pinfunction "2_2") (pintype "passive"))
      (node (ref "U1") (pin "16") (pinfunction "PC1_16") (pintype "passive"))
    )
    (net (code "53") (name "/M_PC2") (class "Default")
      (node (ref "R57") (pin "1") (pinfunction "1_1") (pintype "passive"))
      (node (ref "U1") (pin "17") (pinfunction "PC2_17") (pintype "passive"))
    )
    (net (code "54") (name "/M_PC3") (class "Default")
      (node (ref "C61") (pin "2") (pinfunction "2_2") (pintype "passive"))
      (node (ref "R42") (pin "2") (pinfunction "2_2") (pintype "passive"))
      (node (ref "R67") (pin "1") (pinfunction "1_1") (pintype "passive"))
      (node (ref "U1") (pin "18") (pinfunction "PC3_18") (pintype "passive"))
    )
    (net (code "55") (name "/M_PC4") (class "Default")
      (node (ref "C58") (pin "2") (pinfunction "2_2") (pintype "passive"))
      (node (ref "R36") (pin "1") (pinfunction "1_1") (pintype "passive"))
      (node (ref "R41") (pin "2") (pinfunction "2_2") (pintype "passive"))
      (node (ref "U1") (pin "33") (pinfunction "PC4_33") (pintype "passive"))
    )
    (net (code "56") (name "/M_PC5") (class "Default")
      (node (ref "C57") (pin "2") (pinfunction "2_2") (pintype "passive"))
      (node (ref "R33") (pin "1") (pinfunction "1_1") (pintype "passive"))
      (node (ref "R40") (pin "2") (pinfunction "2_2") (pintype "passive"))
      (node (ref "U1") (pin "34") (pinfunction "PC5_34") (pintype "passive"))
    )
    (net (code "57") (name "/M_PC6") (class "Default")
      (node (ref "R70") (pin "2") (pinfunction "2_2") (pintype "passive"))
      (node (ref "U1") (pin "63") (pinfunction "PC6_63") (pintype "passive"))
    )
    (net (code "58") (name "/M_PC7") (class "Default")
      (node (ref "R19") (pin "2") (pinfunction "2_2") (pintype "passive"))
      (node (ref "U1") (pin "64") (pinfunction "PC7_64") (pintype "passive"))
    )
    (net (code "59") (name "/M_PC8") (class "Default")
      (node (ref "J10") (pin "7") (pinfunction "D0_7") (pintype "passive"))
      (node (ref "R49") (pin "2") (pinfunction "2_2") (pintype "passive"))
      (node (ref "U1") (pin "65") (pinfunction "PC8_65") (pintype "passive"))
    )
    (net (code "60") (name "/M_PC9") (class "Default")
      (node (ref "J10") (pin "8") (pinfunction "D1_8") (pintype "passive"))
      (node (ref "R48") (pin "2") (pinfunction "2_2") (pintype "passive"))
      (node (ref "U1") (pin "66") (pinfunction "PC9_66") (pintype "passive"))
    )
    (net (code "61") (name "/M_PC10") (class "Default")
      (node (ref "J10") (pin "1") (pinfunction "D2_1") (pintype "passive"))
      (node (ref "R52") (pin "2") (pinfunction "2_2") (pintype "passive"))
      (node (ref "U1") (pin "78") (pinfunction "PC10_78") (pintype "passive"))
    )
    (net (code "62") (name "/M_PC11") (class "Default")
      (node (ref "J10") (pin "2") (pinfunction "D3_2") (pintype "passive"))
      (node (ref "R51") (pin "2") (pinfunction "2_2") (pintype "passive"))
      (node (ref "U1") (pin "79") (pinfunction "PC11_79") (pintype "passive"))
    )
    (net (code "63") (name "/M_PC12") (class "Default")
      (node (ref "J10") (pin "5") (pinfunction "CLK_5") (pintype "passive"))
      (node (ref "U1") (pin "80") (pinfunction "PC12_80") (pintype "passive"))
    )
    (net (code "64") (name "/M_PC13") (class "Default")
      (node (ref "J11") (pin "3") (pinfunction "3_3") (pintype "passive"))
      (node (ref "U1") (pin "7") (pinfunction "PC13_7") (pintype "passive"))
      (node (ref "U8") (pin "11") (pinfunction "INT1_11") (pintype "passive"))
    )
    (net (code "65") (name "/M_PC14") (class "Default")
      (node (ref "J11") (pin "4") (pinfunction "4_4") (pintype "passive"))
      (node (ref "U1") (pin "8") (pinfunction "PC14_8") (pintype "passive"))
      (node (ref "U8") (pin "9") (pinfunction "INT2_9") (pintype "passive"))
    )
    (net (code "66") (name "/M_PC15") (class "Default")
      (node (ref "MS1") (pin "4") (pinfunction "CSB_4") (pintype "passive"))
      (node (ref "MS1") (pin "5") (pinfunction "CSB_5") (pintype "passive"))
      (node (ref "U1") (pin "9") (pinfunction "PC15_9") (pintype "passive"))
    )
    (net (code "67") (name "/M_PD0") (class "Default")
      (node (ref "U1") (pin "81") (pinfunction "PD0_81") (pintype "passive"))
      (node (ref "U7") (pin "4") (pinfunction "RXD_4") (pintype "passive"))
    )
    (net (code "68") (name "/M_PD1") (class "Default")
      (node (ref "U1") (pin "82") (pinfunction "PD1_82") (pintype "passive"))
      (node (ref "U7") (pin "1") (pinfunction "TXD_1") (pintype "passive"))
    )
    (net (code "69") (name "/M_PD2") (class "Default")
      (node (ref "J10") (pin "3") (pinfunction "CMD_3") (pintype "passive"))
      (node (ref "R50") (pin "2") (pinfunction "2_2") (pintype "passive"))
      (node (ref "U1") (pin "83") (pinfunction "PD2_83") (pintype "passive"))
    )
    (net (code "70") (name "/M_PD3") (class "Default")
      (node (ref "R23") (pin "2") (pinfunction "2_2") (pintype "passive"))
      (node (ref "U1") (pin "84") (pinfunction "PD3_84") (pintype "passive"))
    )
    (net (code "71") (name "/M_PD4") (class "Default")
      (node (ref "R25") (pin "2") (pinfunction "2_2") (pintype "passive"))
      (node (ref "U1") (pin "85") (pinfunction "PD4_85") (pintype "passive"))
    )
    (net (code "72") (name "/M_PD5") (class "Default")
      (node (ref "R27") (pin "2") (pinfunction "2_2") (pintype "passive"))
      (node (ref "U1") (pin "86") (pinfunction "PD5_86") (pintype "passive"))
    )
    (net (code "73") (name "/M_PD6") (class "Default")
      (node (ref "R29") (pin "2") (pinfunction "2_2") (pintype "passive"))
      (node (ref "U1") (pin "87") (pinfunction "PD6_87") (pintype "passive"))
    )
    (net (code "74") (name "/M_PD7") (class "Default")
      (node (ref "NRF1") (pin "5") (pinfunction "5_5") (pintype "passive"))
      (node (ref "U1") (pin "88") (pinfunction "PD7_88") (pintype "passive"))
    )
    (net (code "75") (name "/M_PD8") (class "Default")
      (node (ref "U1") (pin "55") (pinfunction "PD8_55") (pintype "passive"))
      (node (ref "U3") (pin "20") (pinfunction "RXD_20") (pintype "passive"))
    )
    (net (code "76") (name "/M_PD9") (class "Default")
      (node (ref "U1") (pin "56") (pinfunction "PD9_56") (pintype "passive"))
      (node (ref "U3") (pin "21") (pinfunction "TXD_21") (pintype "passive"))
    )
    (net (code "77") (name "/M_PD10") (class "Default")
      (node (ref "NRF1") (pin "9") (pinfunction "9_9") (pintype "passive"))
      (node (ref "U1") (pin "57") (pinfunction "PD10_57") (pintype "passive"))
    )
    (net (code "78") (name "/M_PD11") (class "Default")
      (node (ref "J11") (pin "6") (pinfunction "6_6") (pintype "passive"))
      (node (ref "U1") (pin "58") (pinfunction "PD11_58") (pintype "passive"))
      (node (ref "U8") (pin "8") (pinfunction "CS_8") (pintype "passive"))
    )
    (net (code "79") (name "/M_PD12") (class "Default")
      (node (ref "R28") (pin "2") (pinfunction "2_2") (pintype "passive"))
      (node (ref "U1") (pin "59") (pinfunction "PD12_59") (pintype "passive"))
    )
    (net (code "80") (name "/M_PD13") (class "Default")
      (node (ref "R26") (pin "2") (pinfunction "2_2") (pintype "passive"))
      (node (ref "U1") (pin "60") (pinfunction "PD13_60") (pintype "passive"))
    )
    (net (code "81") (name "/M_PD14") (class "Default")
      (node (ref "R24") (pin "2") (pinfunction "2_2") (pintype "passive"))
      (node (ref "U1") (pin "61") (pinfunction "PD14_61") (pintype "passive"))
    )
    (net (code "82") (name "/M_PD15") (class "Default")
      (node (ref "R22") (pin "2") (pinfunction "2_2") (pintype "passive"))
      (node (ref "U1") (pin "62") (pinfunction "PD15_62") (pintype "passive"))
    )
    (net (code "83") (name "/M_PE2") (class "Default")
      (node (ref "J11") (pin "10") (pinfunction "10_10") (pintype "passive"))
      (node (ref "MS1") (pin "8") (pinfunction "SCK_8") (pintype "passive"))
      (node (ref "U1") (pin "1") (pinfunction "PE2_1") (pintype "passive"))
      (node (ref "U4") (pin "23") (pinfunction "SCL/SCLK_23") (pintype "passive"))
      (node (ref "U8") (pin "4") (pinfunction "SCL/SPC_4") (pintype "passive"))
      (node (ref "U9") (pin "2") (pinfunction "SCL/SPC_2") (pintype "passive"))
    )
    (net (code "84") (name "/M_PE3") (class "Default")
      (node (ref "J11") (pin "7") (pinfunction "7_7") (pintype "passive"))
      (node (ref "U1") (pin "2") (pinfunction "PE3_2") (pintype "passive"))
      (node (ref "U4") (pin "22") (pinfunction "nCS_22") (pintype "passive"))
    )
    (net (code "85") (name "/M_PE4") (class "Default")
      (node (ref "U1") (pin "3") (pinfunction "PE4_3") (pintype "passive"))
      (node (ref "U9") (pin "6") (pinfunction "DRDY/INT2_6") (pintype "passive"))
    )
    (net (code "86") (name "/M_PE5") (class "Default")
      (node (ref "J11") (pin "9") (pinfunction "9_9") (pintype "passive"))
      (node (ref "MS1") (pin "6") (pinfunction "SDO_6") (pintype "passive"))
      (node (ref "U1") (pin "4") (pinfunction "PE5_4") (pintype "passive"))
      (node (ref "U4") (pin "9") (pinfunction "AD0/SDO_9") (pintype "passive"))
      (node (ref "U8") (pin "7") (pinfunction "SDO/SA0_7") (pintype "passive"))
      (node (ref "U9") (pin "4") (pinfunction "SDO/SA0_4") (pintype "passive"))
    )
    (net (code "87") (name "/M_PE6") (class "Default")
      (node (ref "J11") (pin "8") (pinfunction "8_8") (pintype "passive"))
      (node (ref "MS1") (pin "7") (pinfunction "SDA_7") (pintype "passive"))
      (node (ref "U1") (pin "5") (pinfunction "PE6_5") (pintype "passive"))
      (node (ref "U4") (pin "24") (pinfunction "SDA/SDI_24") (pintype "passive"))
      (node (ref "U8") (pin "6") (pinfunction "SDA/SDI/SDO_6") (pintype "passive"))
      (node (ref "U9") (pin "3") (pinfunction "SDA/SDI/SDO_3") (pintype "passive"))
    )
    (net (code "88") (name "/M_PE7") (class "Default")
      (node (ref "R31") (pin "2") (pinfunction "2_2") (pintype "passive"))
      (node (ref "R76") (pin "1") (pinfunction "1_1") (pintype "passive"))
      (node (ref "R77") (pin "2") (pinfunction "2_2") (pintype "passive"))
      (node (ref "U1") (pin "38") (pinfunction "PE7_38") (pintype "passive"))
    )
    (net (code "89") (name "/M_PE8") (class "Default")
      (node (ref "R34") (pin "2") (pinfunction "2_2") (pintype "passive"))
      (node (ref "R78") (pin "1") (pinfunction "1_1") (pintype "passive"))
      (node (ref "R79") (pin "2") (pinfunction "2_2") (pintype "passive"))
      (node (ref "U1") (pin "39") (pinfunction "PE8_39") (pintype "passive"))
    )
    (net (code "90") (name "/M_PE9") (class "Default")
      (node (ref "R37") (pin "2") (pinfunction "2_2") (pintype "passive"))
      (node (ref "U1") (pin "40") (pinfunction "PE9_40") (pintype "passive"))
    )
    (net (code "91") (name "/M_PE10") (class "Default")
      (node (ref "J11") (pin "5") (pinfunction "5_5") (pintype "passive"))
      (node (ref "U1") (pin "41") (pinfunction "PE10_41") (pintype "passive"))
      (node (ref "U4") (pin "12") (pinfunction "INT_12") (pintype "passive"))
    )
    (net (code "92") (name "/M_PE11") (class "Default")
      (node (ref "R35") (pin "2") (pinfunction "2_2") (pintype "passive"))
      (node (ref "U1") (pin "42") (pinfunction "PE11_42") (pintype "passive"))
    )
    (net (code "93") (name "/M_PE12") (class "Default")
      (node (ref "U1") (pin "43") (pinfunction "PE12_43") (pintype "passive"))
      (node (ref "U6") (pin "1") (pinfunction "~{CS}_1") (pintype "passive"))
    )
    (net (code "94") (name "/M_PE13") (class "Default")
      (node (ref "R32") (pin "2") (pinfunction "2_2") (pintype "passive"))
      (node (ref "U1") (pin "44") (pinfunction "PE13_44") (pintype "passive"))
    )
    (net (code "95") (name "/M_PE14") (class "Default")
      (node (ref "R30") (pin "2") (pinfunction "2_2") (pintype "passive"))
      (node (ref "U1") (pin "45") (pinfunction "PE14_45") (pintype "passive"))
    )
    (net (code "96") (name "/M_PE15") (class "Default")
      (node (ref "NRF1") (pin "4") (pinfunction "4_4") (pintype "passive"))
      (node (ref "U1") (pin "46") (pinfunction "PE15_46") (pintype "passive"))
    )
    (net (code "97") (name "/OSC1") (class "Default")
      (node (ref "C11") (pin "2") (pinfunction "2_2") (pintype "passive"))
      (node (ref "U1") (pin "12") (pinfunction "PH0/OSC_IN_12") (pintype "passive"))
      (node (ref "XT1") (pin "2") (pinfunction "OSC2_2") (pintype "passive"))
    )
    (net (code "98") (name "/OSC2") (class "Default")
      (node (ref "C12") (pin "2") (pinfunction "2_2") (pintype "passive"))
      (node (ref "U1") (pin "13") (pinfunction "PH1/OSC_OUT_13") (pintype "passive"))
      (node (ref "XT1") (pin "1") (pinfunction "OSC1_1") (pintype "passive"))
    )
    (net (code "99") (name "/OUT_3V3") (class "Default")
      (node (ref "C64") (pin "1") (pinfunction "1_1") (pintype "passive"))
      (node (ref "HDR2") (pin "2") (pinfunction "2_2") (pintype "passive"))
      (node (ref "L7") (pin "2") (pinfunction "2_2") (pintype "passive"))
    )
    (net (code "100") (name "/RST") (class "Default")
      (node (ref "C14") (pin "1") (pinfunction "1_1") (pintype "passive"))
      (node (ref "R2") (pin "1") (pinfunction "1_1") (pintype "passive"))
      (node (ref "RST1") (pin "2") (pinfunction "2_2") (pintype "passive"))
      (node (ref "RST1") (pin "4") (pinfunction "4_4") (pintype "passive"))
      (node (ref "U1") (pin "14") (pinfunction "NRST_14") (pintype "passive"))
      (node (ref "U15") (pin "4") (pinfunction "~{RESET}_4") (pintype "passive"))
    )
    (net (code "101") (name "/SBUS_TX") (class "Default")
      (node (ref "R71") (pin "1") (pinfunction "1_1") (pintype "passive"))
      (node (ref "U12") (pin "2") (pinfunction "1B_2") (pintype "passive"))
    )
    (net (code "102") (name "/SPEAKER") (class "Default")
      (node (ref "C60") (pin "2") (pinfunction "2_2") (pintype "passive"))
      (node (ref "R39") (pin "2") (pinfunction "2_2") (pintype "passive"))
      (node (ref "R61") (pin "2") (pinfunction "2_2") (pintype "passive"))
      (node (ref "U11") (pin "4") (pintype "passive"))
    )
    (net (code "103") (name "/VCAP1") (class "Default")
      (node (ref "C44") (pin "1") (pinfunction "1_1") (pintype "passive"))
      (node (ref "C45") (pin "1") (pinfunction "1_1") (pintype "passive"))
      (node (ref "U1") (pin "49") (pinfunction "VCAP_1_49") (pintype "passive"))
    )
    (net (code "104") (name "/VCAP2") (class "Default")
      (node (ref "C13") (pin "2") (pinfunction "2_2") (pintype "passive"))
      (node (ref "C15") (pin "1") (pinfunction "1_1") (pintype "passive"))
      (node (ref "U1") (pin "73") (pinfunction "VCAP_2_73") (pintype "passive"))
    )
    (net (code "106") (name "3V3") (class "Default")
      (node (ref "C18") (pin "1") (pinfunction "1_1") (pintype "passive"))
      (node (ref "C2") (pin "1") (pinfunction "1_1") (pintype "passive"))
      (node (ref "C21") (pin "2") (pinfunction "2_2") (pintype "passive"))
      (node (ref "C25") (pin "1") (pinfunction "1_1") (pintype "passive"))
      (node (ref "C3") (pin "1") (pinfunction "1_1") (pintype "passive"))
      (node (ref "C31") (pin "1") (pinfunction "1_1") (pintype "passive"))
      (node (ref "C36") (pin "1") (pinfunction "1_1") (pintype "passive"))
      (node (ref "C4") (pin "1") (pinfunction "1_1") (pintype "passive"))
      (node (ref "C43") (pin "2") (pinfunction "2_2") (pintype "passive"))
      (node (ref "C46") (pin "2") (pinfunction "2_2") (pintype "passive"))
      (node (ref "C5") (pin "1") (pinfunction "1_1") (pintype "passive"))
      (node (ref "C6") (pin "1") (pinfunction "1_1") (pintype "passive"))
      (node (ref "C62") (pin "1") (pinfunction "1_1") (pintype "passive"))
      (node (ref "C66") (pin "1") (pinfunction "1_1") (pintype "passive"))
      (node (ref "C67") (pin "2") (pinfunction "2_2") (pintype "passive"))
      (node (ref "C7") (pin "1") (pinfunction "1_1") (pintype "passive"))
      (node (ref "C8") (pin "1") (pinfunction "1_1") (pintype "passive"))
      (node (ref "D1") (pin "A") (pintype "passive"))
      (node (ref "D5") (pin "2") (pinfunction "A_2") (pintype "passive"))
      (node (ref "J10") (pin "4") (pinfunction "VCC_4") (pintype "passive"))
      (node (ref "L13") (pin "1") (pinfunction "1_1") (pintype "passive"))
      (node (ref "L2") (pin "2") (pinfunction "2_2") (pintype "passive"))
      (node (ref "MS1") (pin "1") (pinfunction "VDD_1") (pintype "passive"))
      (node (ref "R11") (pin "2") (pinfunction "2_2") (pintype "passive"))
      (node (ref "R12") (pin "1") (pinfunction "1_1") (pintype "passive"))
      (node (ref "R2") (pin "2") (pinfunction "2_2") (pintype "passive"))
      (node (ref "R43") (pin "1") (pinfunction "1_1") (pintype "passive"))
      (node (ref "R44") (pin "1") (pinfunction "1_1") (pintype "passive"))
      (node (ref "R48") (pin "1") (pinfunction "1_1") (pintype "passive"))
      (node (ref "R49") (pin "1") (pinfunction "1_1") (pintype "passive"))
      (node (ref "R50") (pin "1") (pinfunction "1_1") (pintype "passive"))
      (node (ref "R51") (pin "1") (pinfunction "1_1") (pintype "passive"))
      (node (ref "R52") (pin "1") (pinfunction "1_1") (pintype "passive"))
      (node (ref "R62") (pin "2") (pinfunction "2_2") (pintype "passive"))
      (node (ref "R72") (pin "2") (pinfunction "2_2") (pintype "passive"))
      (node (ref "R74") (pin "2") (pinfunction "2_2") (pintype "passive"))
      (node (ref "R76") (pin "2") (pinfunction "2_2") (pintype "passive"))
      (node (ref "R78") (pin "2") (pinfunction "2_2") (pintype "passive"))
      (node (ref "SWD1") (pin "1") (pinfunction "1_1") (pintype "passive"))
      (node (ref "U1") (pin "100") (pinfunction "VDD_100") (pintype "passive"))
      (node (ref "U1") (pin "11") (pinfunction "VDD_11") (pintype "passive"))
      (node (ref "U1") (pin "19") (pinfunction "VDD_19") (pintype "passive"))
      (node (ref "U1") (pin "28") (pinfunction "VDD_28") (pintype "passive"))
      (node (ref "U1") (pin "50") (pinfunction "VDD_50") (pintype "passive"))
      (node (ref "U1") (pin "75") (pinfunction "VDD_75") (pintype "passive"))
      (node (ref "U12") (pin "8") (pinfunction "VCC_8") (pintype "passive"))
      (node (ref "U14") (pin "8") (pinfunction "VCC_8") (pintype "passive"))
      (node (ref "U15") (pin "1") (pinfunction "~{SHDN}_1") (pintype "passive"))
      (node (ref "U15") (pin "10") (pinfunction "VIN_10") (pintype "passive"))
      (node (ref "U2") (pin "2") (pinfunction "OUT_2") (pintype "passive"))
      (node (ref "U4") (pin "8") (pinfunction "VDDIO_8") (pintype "passive"))
      (node (ref "U5") (pin "13") (pinfunction "VDDIO_13") (pintype "passive"))
      (node (ref "U5") (pin "4") (pinfunction "S1_4") (pintype "passive"))
      (node (ref "U6") (pin "3") (pinfunction "~{W}P_3") (pintype "passive"))
      (node (ref "U6") (pin "7") (pinfunction "~{HOLD}_7") (pintype "passive"))
      (node (ref "U6") (pin "8") (pinfunction "VDD_8") (pintype "passive"))
      (node (ref "U7") (pin "3") (pinfunction "VCC_3") (pintype "passive"))
      (node (ref "U8") (pin "1") (pinfunction "Vdd_IO_1") (pintype "passive"))
      (node (ref "U9") (pin "1") (pinfunction "Vdd_IO_1") (pintype "passive"))
    )
    (net (code "107") (name "3V3_Sensor") (class "Default")
      (node (ref "C20") (pin "1") (pinfunction "1_1") (pintype "passive"))
      (node (ref "C22") (pin "1") (pinfunction "1_1") (pintype "passive"))
      (node (ref "C24") (pin "2") (pinfunction "2_2") (pintype "passive"))
      (node (ref "C49") (pin "2") (pinfunction "2_2") (pintype "passive"))
      (node (ref "C50") (pin "2") (pinfunction "2_2") (pintype "passive"))
      (node (ref "C51") (pin "2") (pinfunction "2_2") (pintype "passive"))
      (node (ref "C52") (pin "2") (pinfunction "2_2") (pintype "passive"))
      (node (ref "C9") (pin "1") (pinfunction "1_1") (pintype "passive"))
      (node (ref "L2") (pin "1") (pinfunction "1_1") (pintype "passive"))
      (node (ref "U1") (pin "21") (pinfunction "VREF+_21") (pintype "passive"))
      (node (ref "U1") (pin "22") (pinfunction "VDDA_22") (pintype "passive"))
      (node (ref "U4") (pin "13") (pinfunction "VDD_13") (pintype "passive"))
      (node (ref "U5") (pin "2") (pinfunction "VDD_2") (pintype "passive"))
      (node (ref "U8") (pin "14") (pinfunction "Vdd_14") (pintype "passive"))
      (node (ref "U9") (pin "15") (pinfunction "Reserved_15") (pintype "passive"))
      (node (ref "U9") (pin "16") (pinfunction "Vdd_16") (pintype "passive"))
    )
    (net (code "108") (name "5V0_P") (class "Default")
      (node (ref "C10") (pin "1") (pinfunction "1_1") (pintype "passive"))
      (node (ref "C29") (pin "1") (pinfunction "1_1") (pintype "passive"))
      (node (ref "C32") (pin "1") (pinfunction "1_1") (pintype "passive"))
      (node (ref "C34") (pin "1") (pinfunction "1_1") (pintype "passive"))
      (node (ref "C37") (pin "1") (pinfunction "1_1") (pintype "passive"))
      (node (ref "C38") (pin "1") (pinfunction "1_1") (pintype "passive"))
      (node (ref "C39") (pin "1") (pinfunction "1_1") (pintype "passive"))
      (node (ref "C47") (pin "1") (pinfunction "1_1") (pintype "passive"))
      (node (ref "C48") (pin "2") (pinfunction "2_2") (pintype "passive"))
      (node (ref "L10") (pin "1") (pinfunction "1_1") (pintype "passive"))
      (node (ref "L11") (pin "1") (pinfunction "1_1") (pintype "passive"))
      (node (ref "L12") (pin "1") (pinfunction "1_1") (pintype "passive"))
      (node (ref "L16") (pin "1") (pinfunction "1_1") (pintype "passive"))
      (node (ref "L3") (pin "2") (pinfunction "2_2") (pintype "passive"))
      (node (ref "L5") (pin "2") (pinfunction "2_2") (pintype "passive"))
      (node (ref "L6") (pin "1") (pinfunction "1_1") (pintype "passive"))
      (node (ref "L8") (pin "1") (pinfunction "1_1") (pintype "passive"))
      (node (ref "R47") (pin "1") (pinfunction "1_1") (pintype "passive"))
      (node (ref "R64") (pin "1") (pinfunction "1_1") (pintype "passive"))
      (node (ref "U3") (pin "7") (pinfunction "REGIN_7") (pintype "passive"))
    )
    (net (code "109") (name "5V0_S") (class "Default")
      (node (ref "C1") (pin "1") (pinfunction "1_1") (pintype "passive"))
      (node (ref "HDR2") (pin "1") (pinfunction "1_1") (pintype "passive"))
      (node (ref "HDR2") (pin "10") (pinfunction "10_10") (pintype "passive"))
      (node (ref "HDR2") (pin "11") (pinfunction "11_11") (pintype "passive"))
      (node (ref "HDR2") (pin "12") (pinfunction "12_12") (pintype "passive"))
      (node (ref "HDR2") (pin "13") (pinfunction "13_13") (pintype "passive"))
      (node (ref "HDR2") (pin "14") (pinfunction "14_14") (pintype "passive"))
      (node (ref "HDR2") (pin "15") (pinfunction "15_15") (pintype "passive"))
      (node (ref "HDR2") (pin "7") (pinfunction "7_7") (pintype "passive"))
      (node (ref "HDR2") (pin "8") (pinfunction "8_8") (pintype "passive"))
      (node (ref "HDR2") (pin "9") (pinfunction "9_9") (pintype "passive"))
      (node (ref "L1") (pin "2") (pinfunction "2_2") (pintype "passive"))
    )
    (net (code "110") (name "5V_In") (class "Default")
      (node (ref "C16") (pin "1") (pinfunction "1_1") (pintype "passive"))
      (node (ref "C17") (pin "1") (pinfunction "1_1") (pintype "passive"))
      (node (ref "C65") (pin "1") (pinfunction "1_1") (pintype "passive"))
      (node (ref "C68") (pin "1") (pinfunction "1_1") (pintype "passive"))
      (node (ref "D3") (pin "K") (pintype "passive"))
      (node (ref "L1") (pin "1") (pinfunction "1_1") (pintype "passive"))
      (node (ref "L3") (pin "1") (pinfunction "1_1") (pintype "passive"))
      (node (ref "L4") (pin "1") (pinfunction "1_1") (pintype "passive"))
      (node (ref "LED1") (pin "A1") (pinfunction "A1_A1") (pintype "passive"))
      (node (ref "LED1") (pin "A2") (pinfunction "A2_A2") (pintype "passive"))
      (node (ref "LED1") (pin "A3") (pinfunction "A3_A3") (pintype "passive"))
      (node (ref "R10") (pin "1") (pinfunction "1_1") (pintype "passive"))
      (node (ref "U10") (pin "4") (pinfunction "EN_4") (pintype "passive"))
      (node (ref "U10") (pin "6") (pinfunction "VIN_6") (pintype "passive"))
      (node (ref "U13") (pin "3") (pinfunction "IN_3") (pintype "passive"))
      (node (ref "U2") (pin "3") (pinfunction "IN_3") (pintype "passive"))
    )
    (net (code "111") (name "GND") (class "Default")
      (node (ref "BT1") (pin "2") (pinfunction "-_2") (pintype "passive"))
      (node (ref "C1") (pin "2") (pinfunction "2_2") (pintype "passive"))
      (node (ref "C10") (pin "2") (pinfunction "2_2") (pintype "passive"))
      (node (ref "C11") (pin "1") (pinfunction "1_1") (pintype "passive"))
      (node (ref "C12") (pin "1") (pinfunction "1_1") (pintype "passive"))
      (node (ref "C13") (pin "1") (pinfunction "1_1") (pintype "passive"))
      (node (ref "C14") (pin "2") (pinfunction "2_2") (pintype "passive"))
      (node (ref "C15") (pin "2") (pinfunction "2_2") (pintype "passive"))
      (node (ref "C16") (pin "2") (pinfunction "2_2") (pintype "passive"))
      (node (ref "C17") (pin "2") (pinfunction "2_2") (pintype "passive"))
      (node (ref "C18") (pin "2") (pinfunction "2_2") (pintype "passive"))
      (node (ref "C19") (pin "2") (pinfunction "2_2") (pintype "passive"))
      (node (ref "C2") (pin "2") (pinfunction "2_2") (pintype "passive"))
      (node (ref "C20") (pin "2") (pinfunction "2_2") (pintype "passive"))
      (node (ref "C21") (pin "1") (pinfunction "1_1") (pintype "passive"))
      (node (ref "C22") (pin "2") (pinfunction "2_2") (pintype "passive"))
      (node (ref "C23") (pin "1") (pinfunction "1_1") (pintype "passive"))
      (node (ref "C24") (pin "1") (pinfunction "1_1") (pintype "passive"))
      (node (ref "C25") (pin "2") (pinfunction "2_2") (pintype "passive"))
      (node (ref "C26") (pin "1") (pinfunction "1_1") (pintype "passive"))
      (node (ref "C27") (pin "1") (pinfunction "1_1") (pintype "passive"))
      (node (ref "C29") (pin "2") (pinfunction "2_2") (pintype "passive"))
      (node (ref "C3") (pin "2") (pinfunction "2_2") (pintype "passive"))
      (node (ref "C30") (pin "1") (pinfunction "1_1") (pintype "passive"))
      (node (ref "C31") (pin "2") (pinfunction "2_2") (pintype "passive"))
      (node (ref "C32") (pin "2") (pinfunction "2_2") (pintype "passive"))
      (node (ref "C33") (pin "1") (pinfunction "1_1") (pintype "passive"))
      (node (ref "C34") (pin "2") (pinfunction "2_2") (pintype "passive"))
      (node (ref "C35") (pin "1") (pinfunction "1_1") (pintype "passive"))
      (node (ref "C36") (pin "2") (pinfunction "2_2") (pintype "passive"))
      (node (ref "C37") (pin "2") (pinfunction "2_2") (pintype "passive"))
      (node (ref "C38") (pin "2") (pinfunction "2_2") (pintype "passive"))
      (node (ref "C39") (pin "2") (pinfunction "2_2") (pintype "passive"))
      (node (ref "C4") (pin "2") (pinfunction "2_2") (pintype "passive"))
      (node (ref "C40") (pin "1") (pinfunction "1_1") (pintype "passive"))
      (node (ref "C41") (pin "2") (pinfunction "2_2") (pintype "passive"))
      (node (ref "C42") (pin "2") (pinfunction "2_2") (pintype "passive"))
      (node (ref "C43") (pin "1") (pinfunction "1_1") (pintype "passive"))
      (node (ref "C44") (pin "2") (pinfunction "2_2") (pintype "passive"))
      (node (ref "C45") (pin "2") (pinfunction "2_2") (pintype "passive"))
      (node (ref "C46") (pin "1") (pinfunction "1_1") (pintype "passive"))
      (node (ref "C47") (pin "2") (pinfunction "2_2") (pintype "passive"))
      (node (ref "C48") (pin "1") (pinfunction "1_1") (pintype "passive"))
      (node (ref "C49") (pin "1") (pinfunction "1_1") (pintype "passive"))
      (node (ref "C5") (pin "2") (pinfunction "2_2") (pintype "passive"))
      (node (ref "C50") (pin "1") (pinfunction "1_1") (pintype "passive"))
      (node (ref "C51") (pin "1") (pinfunction "1_1") (pintype "passive"))
      (node (ref "C52") (pin "1") (pinfunction "1_1") (pintype "passive"))
      (node (ref "C54") (pin "1") (pinfunction "1_1") (pintype "passive"))
      (node (ref "C56") (pin "2") (pinfunction "2_2") (pintype "passive"))
      (node (ref "C57") (pin "1") (pinfunction "1_1") (pintype "passive"))
      (node (ref "C58") (pin "1") (pinfunction "1_1") (pintype "passive"))
      (node (ref "C59") (pin "2") (pinfunction "2_2") (pintype "passive"))
      (node (ref "C6") (pin "2") (pinfunction "2_2") (pintype "passive"))
      (node (ref "C61") (pin "1") (pinfunction "1_1") (pintype "passive"))
      (node (ref "C62") (pin "2") (pinfunction "2_2") (pintype "passive"))
      (node (ref "C63") (pin "2") (pinfunction "2_2") (pintype "passive"))
      (node (ref "C64") (pin "2") (pinfunction "2_2") (pintype "passive"))
      (node (ref "C65") (pin "2") (pinfunction "2_2") (pintype "passive"))
      (node (ref "C66") (pin "2") (pinfunction "2_2") (pintype "passive"))
      (node (ref "C67") (pin "1") (pinfunction "1_1") (pintype "passive"))
      (node (ref "C68") (pin "2") (pinfunction "2_2") (pintype "passive"))
      (node (ref "C69") (pin "2") (pinfunction "2_2") (pintype "passive"))
      (node (ref "C7") (pin "2") (pinfunction "2_2") (pintype "passive"))
      (node (ref "C8") (pin "2") (pinfunction "2_2") (pintype "passive"))
      (node (ref "C9") (pin "2") (pinfunction "2_2") (pintype "passive"))
      (node (ref "F1") (pin "2") (pinfunction "GND_2") (pintype "passive"))
      (node (ref "HDR3") (pin "1") (pinfunction "1_1") (pintype "passive"))
      (node (ref "HDR3") (pin "10") (pinfunction "10_10") (pintype "passive"))
      (node (ref "HDR3") (pin "11") (pinfunction "11_11") (pintype "passive"))
      (node (ref "HDR3") (pin "12") (pinfunction "12_12") (pintype "passive"))
      (node (ref "HDR3") (pin "13") (pinfunction "13_13") (pintype "passive"))
      (node (ref "HDR3") (pin "14") (pinfunction "14_14") (pintype "passive"))
      (node (ref "HDR3") (pin "15") (pinfunction "15_15") (pintype "passive"))
      (node (ref "HDR3") (pin "16") (pinfunction "16_16") (pintype "passive"))
      (node (ref "HDR3") (pin "2") (pinfunction "2_2") (pintype "passive"))
      (node (ref "HDR3") (pin "3") (pinfunction "3_3") (pintype "passive"))
      (node (ref "HDR3") (pin "4") (pinfunction "4_4") (pintype "passive"))
      (node (ref "HDR3") (pin "5") (pinfunction "5_5") (pintype "passive"))
      (node (ref "HDR3") (pin "6") (pinfunction "6_6") (pintype "passive"))
      (node (ref "HDR3") (pin "7") (pinfunction "7_7") (pintype "passive"))
      (node (ref "HDR3") (pin "8") (pinfunction "8_8") (pintype "passive"))
      (node (ref "HDR3") (pin "9") (pinfunction "9_9") (pintype "passive"))
      (node (ref "J1") (pin "5") (pinfunction "5_5") (pintype "passive"))
      (node (ref "J10") (pin "6") (pinfunction "GND_6") (pintype "passive"))
      (node (ref "J11") (pin "0") (pinfunction "GND_0") (pintype "passive"))
      (node (ref "J11") (pin "2") (pinfunction "2_2") (pintype "passive"))
      (node (ref "J12") (pin "0") (pinfunction "GND_0") (pintype "passive"))
      (node (ref "J12") (pin "5") (pinfunction "5_5") (pintype "passive"))
      (node (ref "J12") (pin "6") (pinfunction "6_6") (pintype "passive"))
      (node (ref "J2") (pin "0") (pinfunction "GND_0") (pintype "passive"))
      (node (ref "J2") (pin "6") (pinfunction "6_6") (pintype "passive"))
      (node (ref "J3") (pin "0") (pinfunction "GND_0") (pintype "passive"))
      (node (ref "J3") (pin "4") (pinfunction "4_4") (pintype "passive"))
      (node (ref "J4") (pin "0") (pinfunction "GND_0") (pintype "passive"))
      (node (ref "J4") (pin "4") (pinfunction "4_4") (pintype "passive"))
      (node (ref "J6") (pin "0") (pinfunction "GND_0") (pintype "passive"))
      (node (ref "J6") (pin "6") (pinfunction "6_6") (pintype "passive"))
      (node (ref "J7") (pin "0") (pinfunction "GND_0") (pintype "passive"))
      (node (ref "J7") (pin "6") (pinfunction "6_6") (pintype "passive"))
      (node (ref "J8") (pin "0") (pinfunction "GND_0") (pintype "passive"))
      (node (ref "J8") (pin "4") (pinfunction "4_4") (pintype "passive"))
      (node (ref "MS1") (pin "2") (pinfunction "PS_2") (pintype "passive"))
      (node (ref "MS1") (pin "3") (pinfunction "GND_3") (pintype "passive"))
      (node (ref "NRF1") (pin "0") (pinfunction "GND_0") (pintype "passive"))
      (node (ref "NRF1") (pin "10") (pinfunction "10_10") (pintype "passive"))
      (node (ref "PD1") (pin "1") (pintype "passive"))
      (node (ref "R3") (pin "2") (pinfunction "2_2") (pintype "passive"))
      (node (ref "R33") (pin "2") (pinfunction "2_2") (pintype "passive"))
      (node (ref "R36") (pin "2") (pinfunction "2_2") (pintype "passive"))
      (node (ref "R38") (pin "2") (pinfunction "2_2") (pintype "passive"))
      (node (ref "R5") (pin "1") (pinfunction "1_1") (pintype "passive"))
      (node (ref "R58") (pin "2") (pinfunction "2_2") (pintype "passive"))
      (node (ref "R59") (pin "2") (pinfunction "2_2") (pintype "passive"))
      (node (ref "R60") (pin "1") (pinfunction "1_1") (pintype "passive"))
      (node (ref "R66") (pin "2") (pinfunction "2_2") (pintype "passive"))
      (node (ref "R67") (pin "2") (pinfunction "2_2") (pintype "passive"))
      (node (ref "R73") (pin "1") (pinfunction "1_1") (pintype "passive"))
      (node (ref "R75") (pin "1") (pinfunction "1_1") (pintype "passive"))
      (node (ref "R77") (pin "1") (pinfunction "1_1") (pintype "passive"))
      (node (ref "R79") (pin "1") (pinfunction "1_1") (pintype "passive"))
      (node (ref "R9") (pin "1") (pinfunction "1_1") (pintype "passive"))
      (node (ref "RST1") (pin "1") (pinfunction "1_1") (pintype "passive"))
      (node (ref "RST1") (pin "3") (pinfunction "3_3") (pintype "passive"))
      (node (ref "SWD1") (pin "0") (pinfunction "GND_0") (pintype "passive"))
      (node (ref "SWD1") (pin "4") (pinfunction "4_4") (pintype "passive"))
      (node (ref "U1") (pin "10") (pinfunction "VSS_10") (pintype "passive"))
      (node (ref "U1") (pin "20") (pinfunction "VSSA_20") (pintype "passive"))
      (node (ref "U1") (pin "27") (pinfunction "VSS_27") (pintype "passive"))
      (node (ref "U1") (pin "74") (pinfunction "VSS_74") (pintype "passive"))
      (node (ref "U1") (pin "99") (pinfunction "VSS_99") (pintype "passive"))
      (node (ref "U10") (pin "2") (pinfunction "GND_2") (pintype "passive"))
      (node (ref "U11") (pin "2") (pinfunction "V-_2") (pintype "passive"))
      (node (ref "U12") (pin "4") (pinfunction "GND_4") (pintype "passive"))
      (node (ref "U13") (pin "1") (pinfunction "GND_1") (pintype "passive"))
      (node (ref "U14") (pin "4") (pinfunction "GND_4") (pintype "passive"))
      (node (ref "U15") (pin "5") (pinfunction "GND_5") (pintype "passive"))
      (node (ref "U2") (pin "1") (pinfunction "GND_1") (pintype "passive"))
      (node (ref "U3") (pin "2") (pinfunction "GND_2") (pintype "passive"))
      (node (ref "U4") (pin "11") (pinfunction "FSYNC_11") (pintype "passive"))
      (node (ref "U4") (pin "18") (pinfunction "GND_18") (pintype "passive"))
      (node (ref "U4") (pin "20") (pinfunction "RESV_20") (pintype "passive"))
      (node (ref "U5") (pin "11") (pinfunction "GND_11") (pintype "passive"))
      (node (ref "U5") (pin "9") (pinfunction "GND_9") (pintype "passive"))
      (node (ref "U6") (pin "4") (pinfunction "VSS_4") (pintype "passive"))
      (node (ref "U7") (pin "2") (pinfunction "GND_2") (pintype "passive"))
      (node (ref "U7") (pin "8") (pinfunction "RS_8") (pintype "passive"))
      (node (ref "U7") (pin "9") (pinfunction "EPAD_9") (pintype "passive"))
      (node (ref "U8") (pin "10") (pinfunction "Reserved_10") (pintype "passive"))
      (node (ref "U8") (pin "12") (pinfunction "GND_12") (pintype "passive"))
      (node (ref "U8") (pin "13") (pinfunction "GND_13") (pintype "passive"))
      (node (ref "U8") (pin "16") (pinfunction "GND_16") (pintype "passive"))
      (node (ref "U8") (pin "5") (pinfunction "GND_5") (pintype "passive"))
      (node (ref "U9") (pin "10") (pinfunction "Reserved_10") (pintype "passive"))
      (node (ref "U9") (pin "11") (pinfunction "Reserved_11") (pintype "passive"))
      (node (ref "U9") (pin "12") (pinfunction "GND_12") (pintype "passive"))
      (node (ref "U9") (pin "13") (pinfunction "GND_13") (pintype "passive"))
      (node (ref "U9") (pin "9") (pinfunction "Reserved_9") (pintype "passive"))
      (node (ref "USB1") (pin "0") (pinfunction "PGND_0") (pintype "passive"))
      (node (ref "USB1") (pin "5") (pinfunction "GND_5") (pintype "passive"))
      (node (ref "USB2") (pin "0") (pinfunction "PGND_0") (pintype "passive"))
      (node (ref "USB2") (pin "5") (pinfunction "GND_5") (pintype "passive"))
    )
    (net (code "112") (name "Net-(BT1-+)") (class "Default")
      (node (ref "BT1") (pin "1") (pinfunction "+_1") (pintype "passive"))
      (node (ref "C19") (pin "1") (pinfunction "1_1") (pintype "passive"))
      (node (ref "R1") (pin "1") (pinfunction "1_1") (pintype "passive"))
      (node (ref "U1") (pin "6") (pinfunction "VBAT_6") (pintype "passive"))
    )
    (net (code "113") (name "Net-(C41-Pad1)") (class "Default")
      (node (ref "C41") (pin "1") (pinfunction "1_1") (pintype "passive"))
      (node (ref "L15") (pin "1") (pinfunction "1_1") (pintype "passive"))
      (node (ref "R57") (pin "2") (pinfunction "2_2") (pintype "passive"))
    )
    (net (code "114") (name "Net-(C42-Pad1)") (class "Default")
      (node (ref "C42") (pin "1") (pinfunction "1_1") (pintype "passive"))
      (node (ref "L14") (pin "1") (pinfunction "1_1") (pintype "passive"))
      (node (ref "R56") (pin "2") (pinfunction "2_2") (pintype "passive"))
    )
    (net (code "115") (name "Net-(D1-PadK)") (class "Default")
      (node (ref "D1") (pin "K") (pintype "passive"))
      (node (ref "R1") (pin "2") (pinfunction "2_2") (pintype "passive"))
    )
    (net (code "116") (name "Net-(D3-PadA)") (class "Default")
      (node (ref "D3") (pin "A") (pintype "passive"))
      (node (ref "J12") (pin "1") (pinfunction "1_1") (pintype "passive"))
      (node (ref "J12") (pin "2") (pinfunction "2_2") (pintype "passive"))
    )
    (net (code "117") (name "Net-(D5-K)") (class "Default")
      (node (ref "D5") (pin "1") (pinfunction "K_1") (pintype "passive"))
      (node (ref "R14") (pin "2") (pinfunction "2_2") (pintype "passive"))
    )
    (net (code "118") (name "Net-(F1-DI1)") (class "Default")
      (node (ref "F1") (pin "1") (pinfunction "DI1_1") (pintype "passive"))
      (node (ref "USB1") (pin "2") (pinfunction "DM_2") (pintype "passive"))
    )
    (net (code "119") (name "Net-(F1-DI2)") (class "Default")
      (node (ref "F1") (pin "3") (pinfunction "DI2_3") (pintype "passive"))
      (node (ref "USB1") (pin "3") (pinfunction "DP_3") (pintype "passive"))
    )
    (net (code "120") (name "Net-(HDR1-Pad2)") (class "Default")
      (node (ref "HDR1") (pin "2") (pinfunction "2_2") (pintype "passive"))
      (node (ref "R15") (pin "1") (pinfunction "1_1") (pintype "passive"))
    )
    (net (code "121") (name "Net-(HDR1-Pad3)") (class "Default")
      (node (ref "HDR1") (pin "3") (pinfunction "3_3") (pintype "passive"))
      (node (ref "R16") (pin "1") (pinfunction "1_1") (pintype "passive"))
    )
    (net (code "122") (name "Net-(HDR1-Pad4)") (class "Default")
      (node (ref "HDR1") (pin "4") (pinfunction "4_4") (pintype "passive"))
      (node (ref "R17") (pin "1") (pinfunction "1_1") (pintype "passive"))
    )
    (net (code "123") (name "Net-(HDR1-Pad5)") (class "Default")
      (node (ref "HDR1") (pin "5") (pinfunction "5_5") (pintype "passive"))
      (node (ref "R19") (pin "1") (pinfunction "1_1") (pintype "passive"))
    )
    (net (code "124") (name "Net-(HDR1-Pad6)") (class "Default")
      (node (ref "HDR1") (pin "6") (pinfunction "6_6") (pintype "passive"))
      (node (ref "R21") (pin "1") (pinfunction "1_1") (pintype "passive"))
    )
    (net (code "125") (name "Net-(HDR1-Pad7)") (class "Default")
      (node (ref "HDR1") (pin "7") (pinfunction "7_7") (pintype "passive"))
      (node (ref "R22") (pin "1") (pinfunction "1_1") (pintype "passive"))
    )
    (net (code "126") (name "Net-(HDR1-Pad8)") (class "Default")
      (node (ref "HDR1") (pin "8") (pinfunction "8_8") (pintype "passive"))
      (node (ref "R24") (pin "1") (pinfunction "1_1") (pintype "passive"))
    )
    (net (code "127") (name "Net-(HDR1-Pad9)") (class "Default")
      (node (ref "HDR1") (pin "9") (pinfunction "9_9") (pintype "passive"))
      (node (ref "R26") (pin "1") (pinfunction "1_1") (pintype "passive"))
    )
    (net (code "128") (name "Net-(HDR1-Pad10)") (class "Default")
      (node (ref "HDR1") (pin "10") (pinfunction "10_10") (pintype "passive"))
      (node (ref "R28") (pin "1") (pinfunction "1_1") (pintype "passive"))
    )
    (net (code "129") (name "Net-(HDR1-Pad11)") (class "Default")
      (node (ref "HDR1") (pin "11") (pinfunction "11_11") (pintype "passive"))
      (node (ref "R30") (pin "1") (pinfunction "1_1") (pintype "passive"))
    )
    (net (code "130") (name "Net-(HDR1-Pad12)") (class "Default")
      (node (ref "HDR1") (pin "12") (pinfunction "12_12") (pintype "passive"))
      (node (ref "R32") (pin "1") (pinfunction "1_1") (pintype "passive"))
    )
    (net (code "131") (name "Net-(HDR1-Pad13)") (class "Default")
      (node (ref "HDR1") (pin "13") (pinfunction "13_13") (pintype "passive"))
      (node (ref "R35") (pin "1") (pinfunction "1_1") (pintype "passive"))
    )
    (net (code "132") (name "Net-(HDR1-Pad14)") (class "Default")
      (node (ref "HDR1") (pin "14") (pinfunction "14_14") (pintype "passive"))
      (node (ref "R37") (pin "1") (pinfunction "1_1") (pintype "passive"))
    )
    (net (code "133") (name "Net-(HDR1-Pad15)") (class "Default")
      (node (ref "HDR1") (pin "15") (pinfunction "15_15") (pintype "passive"))
      (node (ref "R39") (pin "1") (pinfunction "1_1") (pintype "passive"))
    )
    (net (code "134") (name "Net-(HDR2-Pad3)") (class "Default")
      (node (ref "HDR2") (pin "3") (pinfunction "3_3") (pintype "passive"))
      (node (ref "R83") (pin "1") (pinfunction "1_1") (pintype "passive"))
    )
    (net (code "135") (name "Net-(HDR2-Pad4)") (class "Default")
      (node (ref "HDR2") (pin "4") (pinfunction "4_4") (pintype "passive"))
      (node (ref "R82") (pin "1") (pinfunction "1_1") (pintype "passive"))
    )
    (net (code "136") (name "Net-(HDR2-Pad5)") (class "Default")
      (node (ref "HDR2") (pin "5") (pinfunction "5_5") (pintype "passive"))
      (node (ref "R81") (pin "1") (pinfunction "1_1") (pintype "passive"))
    )
    (net (code "137") (name "Net-(HDR2-Pad6)") (class "Default")
      (node (ref "HDR2") (pin "6") (pinfunction "6_6") (pintype "passive"))
      (node (ref "R80") (pin "1") (pinfunction "1_1") (pintype "passive"))
    )
    (net (code "138") (name "Net-(J1-Pad1)") (class "Default")
      (node (ref "J1") (pin "1") (pinfunction "1_1") (pintype "passive"))
      (node (ref "L5") (pin "1") (pinfunction "1_1") (pintype "passive"))
    )
    (net (code "139") (name "Net-(J1-Pad2)") (class "Default")
      (node (ref "J1") (pin "2") (pinfunction "2_2") (pintype "passive"))
      (node (ref "R40") (pin "1") (pinfunction "1_1") (pintype "passive"))
    )
    (net (code "140") (name "Net-(J1-Pad3)") (class "Default")
      (node (ref "J1") (pin "3") (pinfunction "3_3") (pintype "passive"))
      (node (ref "R41") (pin "1") (pinfunction "1_1") (pintype "passive"))
    )
    (net (code "141") (name "Net-(J1-Pad4)") (class "Default")
      (node (ref "J1") (pin "4") (pinfunction "4_4") (pintype "passive"))
      (node (ref "R42") (pin "1") (pinfunction "1_1") (pintype "passive"))
    )
    (net (code "142") (name "Net-(J2-Pad1)") (class "Default")
      (node (ref "J2") (pin "1") (pinfunction "1_1") (pintype "passive"))
      (node (ref "L6") (pin "2") (pinfunction "2_2") (pintype "passive"))
    )
    (net (code "143") (name "Net-(J3-Pad1)") (class "Default")
      (node (ref "J3") (pin "1") (pinfunction "1_1") (pintype "passive"))
      (node (ref "J4") (pin "1") (pinfunction "1_1") (pintype "passive"))
      (node (ref "L8") (pin "2") (pinfunction "2_2") (pintype "passive"))
    )
    (net (code "144") (name "Net-(J3-Pad2)") (class "Default")
      (node (ref "J3") (pin "2") (pinfunction "2_2") (pintype "passive"))
      (node (ref "J4") (pin "2") (pinfunction "2_2") (pintype "passive"))
      (node (ref "R45") (pin "1") (pinfunction "1_1") (pintype "passive"))
    )
    (net (code "145") (name "Net-(J3-Pad3)") (class "Default")
      (node (ref "J3") (pin "3") (pinfunction "3_3") (pintype "passive"))
      (node (ref "J4") (pin "3") (pinfunction "3_3") (pintype "passive"))
      (node (ref "R46") (pin "1") (pinfunction "1_1") (pintype "passive"))
    )
    (net (code "146") (name "Net-(J6-Pad1)") (class "Default")
      (node (ref "J6") (pin "1") (pinfunction "1_1") (pintype "passive"))
      (node (ref "L10") (pin "2") (pinfunction "2_2") (pintype "passive"))
    )
    (net (code "147") (name "Net-(J6-Pad4)") (class "Default")
      (node (ref "J6") (pin "4") (pinfunction "4_4") (pintype "passive"))
      (node (ref "R53") (pin "1") (pinfunction "1_1") (pintype "passive"))
    )
    (net (code "148") (name "Net-(J6-Pad5)") (class "Default")
      (node (ref "J6") (pin "5") (pinfunction "5_5") (pintype "passive"))
      (node (ref "R54") (pin "1") (pinfunction "1_1") (pintype "passive"))
    )
    (net (code "149") (name "Net-(J7-Pad1)") (class "Default")
      (node (ref "J7") (pin "1") (pinfunction "1_1") (pintype "passive"))
      (node (ref "L11") (pin "2") (pinfunction "2_2") (pintype "passive"))
    )
    (net (code "150") (name "Net-(J7-Pad2)") (class "Default")
      (node (ref "J7") (pin "2") (pinfunction "2_2") (pintype "passive"))
      (node (ref "R18") (pin "1") (pinfunction "1_1") (pintype "passive"))
    )
    (net (code "151") (name "Net-(J7-Pad3)") (class "Default")
      (node (ref "J7") (pin "3") (pinfunction "3_3") (pintype "passive"))
      (node (ref "R20") (pin "1") (pinfunction "1_1") (pintype "passive"))
    )
    (net (code "152") (name "Net-(J8-Pad1)") (class "Default")
      (node (ref "J8") (pin "1") (pinfunction "1_1") (pintype "passive"))
      (node (ref "L12") (pin "2") (pinfunction "2_2") (pintype "passive"))
    )
    (net (code "153") (name "Net-(J11-Pad1)") (class "Default")
      (node (ref "J11") (pin "1") (pinfunction "1_1") (pintype "passive"))
      (node (ref "L13") (pin "2") (pinfunction "2_2") (pintype "passive"))
    )
    (net (code "154") (name "Net-(J12-Pad3)") (class "Default")
      (node (ref "J12") (pin "3") (pinfunction "3_3") (pintype "passive"))
      (node (ref "L14") (pin "2") (pinfunction "2_2") (pintype "passive"))
      (node (ref "R58") (pin "1") (pinfunction "1_1") (pintype "passive"))
    )
    (net (code "155") (name "Net-(J12-Pad4)") (class "Default")
      (node (ref "J12") (pin "4") (pinfunction "4_4") (pintype "passive"))
      (node (ref "L15") (pin "2") (pinfunction "2_2") (pintype "passive"))
      (node (ref "R59") (pin "1") (pinfunction "1_1") (pintype "passive"))
    )
    (net (code "156") (name "Net-(L16-Pad2)") (class "Default")
      (node (ref "L16") (pin "2") (pinfunction "2_2") (pintype "passive"))
      (node (ref "NRF1") (pin "1") (pinfunction "1_1") (pintype "passive"))
    )
    (net (code "157") (name "Net-(R55-Pad1)") (class "Default")
      (node (ref "R55") (pin "1") (pinfunction "1_1") (pintype "passive"))
      (node (ref "R84") (pin "1") (pinfunction "1_1") (pintype "passive"))
      (node (ref "R85") (pin "1") (pinfunction "1_1") (pintype "passive"))
    )
    (net (code "158") (name "Net-(U3-D+)") (class "Default")
      (node (ref "PD1") (pin "4") (pintype "passive"))
      (node (ref "U3") (pin "3") (pinfunction "D+_3") (pintype "passive"))
      (node (ref "USB2") (pin "3") (pinfunction "DP_3") (pintype "passive"))
    )
    (net (code "159") (name "Net-(U3-D-)") (class "Default")
      (node (ref "PD1") (pin "3") (pintype "passive"))
      (node (ref "U3") (pin "4") (pinfunction "D-_4") (pintype "passive"))
      (node (ref "USB2") (pin "2") (pinfunction "DM_2") (pintype "passive"))
    )
    (net (code "160") (name "Net-(U3-VBUS)") (class "Default")
      (node (ref "PD1") (pin "2") (pintype "passive"))
      (node (ref "R64") (pin "2") (pinfunction "2_2") (pintype "passive"))
      (node (ref "U3") (pin "8") (pinfunction "VBUS_8") (pintype "passive"))
      (node (ref "USB2") (pin "1") (pinfunction "VBUS_1") (pintype "passive"))
    )
    (net (code "161") (name "Net-(U3-VPP)") (class "Default")
      (node (ref "C35") (pin "2") (pinfunction "2_2") (pintype "passive"))
      (node (ref "U3") (pin "16") (pinfunction "VPP_16") (pintype "passive"))
    )
    (net (code "162") (name "Net-(U3-~{RST})") (class "Default")
      (node (ref "R63") (pin "1") (pinfunction "1_1") (pintype "passive"))
      (node (ref "U3") (pin "9") (pinfunction "~{RST}_9") (pintype "passive"))
    )
    (net (code "163") (name "Net-(U4-REGOUT)") (class "Default")
      (node (ref "C30") (pin "2") (pinfunction "2_2") (pintype "passive"))
      (node (ref "U4") (pin "10") (pinfunction "REGOUT_10") (pintype "passive"))
    )
    (net (code "164") (name "Net-(U5-C1)") (class "Default")
      (node (ref "C26") (pin "2") (pinfunction "2_2") (pintype "passive"))
      (node (ref "C27") (pin "2") (pinfunction "2_2") (pintype "passive"))
      (node (ref "U5") (pin "10") (pinfunction "C1_10") (pintype "passive"))
    )
    (net (code "165") (name "Net-(U5-SETC)") (class "Default")
      (node (ref "C28") (pin "1") (pinfunction "1_1") (pintype "passive"))
      (node (ref "U5") (pin "12") (pinfunction "SETC_12") (pintype "passive"))
    )
    (net (code "166") (name "Net-(U5-SETP)") (class "Default")
      (node (ref "C28") (pin "2") (pinfunction "2_2") (pintype "passive"))
      (node (ref "U5") (pin "8") (pinfunction "SETP_8") (pintype "passive"))
    )
    (net (code "167") (name "Net-(U7-CANH)") (class "Default")
      (node (ref "J8") (pin "2") (pinfunction "2_2") (pintype "passive"))
      (node (ref "R55") (pin "2") (pinfunction "2_2") (pintype "passive"))
      (node (ref "U7") (pin "7") (pinfunction "CANH_7") (pintype "passive"))
    )
    (net (code "168") (name "Net-(U7-CANL)") (class "Default")
      (node (ref "J8") (pin "3") (pinfunction "3_3") (pintype "passive"))
      (node (ref "R84") (pin "2") (pinfunction "2_2") (pintype "passive"))
      (node (ref "U7") (pin "6") (pinfunction "CANL_6") (pintype "passive"))
    )
    (net (code "169") (name "Net-(U7-SPLIT)") (class "Default")
      (node (ref "C69") (pin "1") (pinfunction "1_1") (pintype "passive"))
      (node (ref "R85") (pin "2") (pinfunction "2_2") (pintype "passive"))
      (node (ref "U7") (pin "5") (pinfunction "SPLIT_5") (pintype "passive"))
    )
    (net (code "170") (name "Net-(U8-C1)") (class "Default")
      (node (ref "C54") (pin "2") (pinfunction "2_2") (pintype "passive"))
      (node (ref "U8") (pin "15") (pinfunction "C1_15") (pintype "passive"))
    )
    (net (code "171") (name "Net-(U8-SETC)") (class "Default")
      (node (ref "C53") (pin "1") (pinfunction "1_1") (pintype "passive"))
      (node (ref "U8") (pin "2") (pinfunction "SETC_2") (pintype "passive"))
    )
    (net (code "172") (name "Net-(U8-SETP)") (class "Default")
      (node (ref "C53") (pin "2") (pinfunction "2_2") (pintype "passive"))
      (node (ref "U8") (pin "3") (pinfunction "SETP_3") (pintype "passive"))
    )
    (net (code "173") (name "Net-(U9-Cap)") (class "Default")
      (node (ref "C23") (pin "2") (pinfunction "2_2") (pintype "passive"))
      (node (ref "U9") (pin "14") (pinfunction "Cap_14") (pintype "passive"))
    )
    (net (code "174") (name "Net-(U10-FB)") (class "Default")
      (node (ref "C55") (pin "2") (pinfunction "2_2") (pintype "passive"))
      (node (ref "R65") (pin "2") (pinfunction "2_2") (pintype "passive"))
      (node (ref "R66") (pin "1") (pinfunction "1_1") (pintype "passive"))
      (node (ref "U10") (pin "3") (pinfunction "FB_3") (pintype "passive"))
    )
    (net (code "175") (name "Net-(U10-LX)") (class "Default")
      (node (ref "D2") (pin "A") (pintype "passive"))
      (node (ref "L4") (pin "2") (pinfunction "2_2") (pintype "passive"))
      (node (ref "U10") (pin "1") (pinfunction "LX_1") (pintype "passive"))
    )
    (net (code "176") (name "Net-(U11--)") (class "Default")
      (node (ref "C60") (pin "1") (pinfunction "1_1") (pintype "passive"))
      (node (ref "R60") (pin "2") (pinfunction "2_2") (pintype "passive"))
      (node (ref "R61") (pin "1") (pinfunction "1_1") (pintype "passive"))
      (node (ref "R62") (pin "1") (pinfunction "1_1") (pintype "passive"))
      (node (ref "U11") (pin "3") (pinfunction "-_3") (pintype "passive"))
    )
    (net (code "177") (name "Net-(U12A-1Y)") (class "Default")
      (node (ref "R68") (pin "1") (pinfunction "1_1") (pintype "passive"))
      (node (ref "U12") (pin "7") (pinfunction "1Y_7") (pintype "passive"))
    )
    (net (code "178") (name "Net-(U12B-2B)") (class "Default")
      (node (ref "R13") (pin "2") (pinfunction "2_2") (pintype "passive"))
      (node (ref "U12") (pin "6") (pinfunction "2B_6") (pintype "passive"))
    )
    (net (code "179") (name "Net-(U13-OUT)") (class "Default")
      (node (ref "C63") (pin "1") (pinfunction "1_1") (pintype "passive"))
      (node (ref "L7") (pin "1") (pinfunction "1_1") (pintype "passive"))
      (node (ref "U13") (pin "2") (pinfunction "OUT_2") (pintype "passive"))
    )
    (net (code "180") (name "Net-(U15-REXT)") (class "Default")
      (node (ref "R3") (pin "1") (pinfunction "1_1") (pintype "passive"))
      (node (ref "U15") (pin "6") (pinfunction "REXT_6") (pintype "passive"))
    )
    (net (code "181") (name "V_SPEAKER") (class "Default")
      (node (ref "C55") (pin "1") (pinfunction "1_1") (pintype "passive"))
      (node (ref "C56") (pin "1") (pinfunction "1_1") (pintype "passive"))
      (node (ref "C59") (pin "1") (pinfunction "1_1") (pintype "passive"))
      (node (ref "D2") (pin "K") (pintype "passive"))
      (node (ref "R65") (pin "1") (pinfunction "1_1") (pintype "passive"))
      (node (ref "U10") (pin "5") (pinfunction "VOUT_5") (pintype "passive"))
      (node (ref "U11") (pin "5") (pinfunction "V+_5") (pintype "passive"))
    )
    (net (code "182") (name "V_USBIO") (class "Default")
      (node (ref "C33") (pin "2") (pinfunction "2_2") (pintype "passive"))
      (node (ref "C40") (pin "2") (pinfunction "2_2") (pintype "passive"))
      (node (ref "R63") (pin "2") (pinfunction "2_2") (pintype "passive"))
      (node (ref "U3") (pin "5") (pinfunction "VIO_5") (pintype "passive"))
      (node (ref "U3") (pin "6") (pinfunction "VDD_6") (pintype "passive"))
    )
    (net (code "183") (name "unconnected-(NRF1-Pad2)") (class "Default")
      (node (ref "NRF1") (pin "2") (pinfunction "2_2") (pintype "passive"))
    )
    (net (code "184") (name "unconnected-(NRF1-Pad3)") (class "Default")
      (node (ref "NRF1") (pin "3") (pinfunction "3_3") (pintype "passive"))
    )
    (net (code "185") (name "unconnected-(R53-Pad2)") (class "Default")
      (node (ref "R53") (pin "2") (pinfunction "2_2") (pintype "passive"))
    )
    (net (code "186") (name "unconnected-(R54-Pad2)") (class "Default")
      (node (ref "R54") (pin "2") (pinfunction "2_2") (pintype "passive"))
    )
    (net (code "187") (name "unconnected-(SC1-GND-Pad0)") (class "Default")
      (node (ref "SC1") (pin "0") (pinfunction "GND_0") (pintype "passive"))
    )
    (net (code "188") (name "unconnected-(SC2-GND-Pad0)") (class "Default")
      (node (ref "SC2") (pin "0") (pinfunction "GND_0") (pintype "passive"))
    )
    (net (code "189") (name "unconnected-(SC3-GND-Pad0)") (class "Default")
      (node (ref "SC3") (pin "0") (pinfunction "GND_0") (pintype "passive"))
    )
    (net (code "190") (name "unconnected-(SC4-GND-Pad0)") (class "Default")
      (node (ref "SC4") (pin "0") (pinfunction "GND_0") (pintype "passive"))
    )
    (net (code "191") (name "unconnected-(U3-CTS-Pad18)") (class "Default")
      (node (ref "U3") (pin "18") (pinfunction "CTS_18") (pintype "passive"))
    )
    (net (code "192") (name "unconnected-(U3-DCD-Pad24)") (class "Default")
      (node (ref "U3") (pin "24") (pinfunction "DCD_24") (pintype "passive"))
    )
    (net (code "193") (name "unconnected-(U3-DSR-Pad22)") (class "Default")
      (node (ref "U3") (pin "22") (pinfunction "DSR_22") (pintype "passive"))
    )
    (net (code "194") (name "unconnected-(U3-DTR-Pad23)") (class "Default")
      (node (ref "U3") (pin "23") (pinfunction "DTR_23") (pintype "passive"))
    )
    (net (code "195") (name "unconnected-(U3-GPIO.0-Pad14)") (class "Default")
      (node (ref "U3") (pin "14") (pinfunction "GPIO.0_14") (pintype "passive"))
    )
    (net (code "196") (name "unconnected-(U3-GPIO.1-Pad13)") (class "Default")
      (node (ref "U3") (pin "13") (pinfunction "GPIO.1_13") (pintype "passive"))
    )
    (net (code "197") (name "unconnected-(U3-GPIO.2-Pad12)") (class "Default")
      (node (ref "U3") (pin "12") (pinfunction "GPIO.2_12") (pintype "passive"))
    )
    (net (code "198") (name "unconnected-(U3-GPIO.3-Pad11)") (class "Default")
      (node (ref "U3") (pin "11") (pinfunction "GPIO.3_11") (pintype "passive"))
    )
    (net (code "199") (name "unconnected-(U3-NC-Pad10)") (class "Default")
      (node (ref "U3") (pin "10") (pinfunction "NC_10") (pintype "passive"))
    )
    (net (code "200") (name "unconnected-(U3-RI-Pad1)") (class "Default")
      (node (ref "U3") (pin "1") (pinfunction "RI_1") (pintype "passive"))
    )
    (net (code "201") (name "unconnected-(U3-RTS-Pad19)") (class "Default")
      (node (ref "U3") (pin "19") (pinfunction "RTS_19") (pintype "passive"))
    )
    (net (code "202") (name "unconnected-(U3-SUSPEND-Pad17)") (class "Default")
      (node (ref "U3") (pin "17") (pinfunction "SUSPEND_17") (pintype "passive"))
    )
    (net (code "203") (name "unconnected-(U3-~{SUSPEND}-Pad15)") (class "Default")
      (node (ref "U3") (pin "15") (pinfunction "~{SUSPEND}_15") (pintype "passive"))
    )
    (net (code "204") (name "unconnected-(U4-AUX_CL-Pad7)") (class "Default")
      (node (ref "U4") (pin "7") (pinfunction "AUX_CL_7") (pintype "passive"))
    )
    (net (code "205") (name "unconnected-(U4-AUX_DA-Pad21)") (class "Default")
      (node (ref "U4") (pin "21") (pinfunction "AUX_DA_21") (pintype "passive"))
    )
    (net (code "206") (name "unconnected-(U4-NC-Pad1)") (class "Default")
      (node (ref "U4") (pin "1") (pinfunction "NC_1") (pintype "passive"))
    )
    (net (code "207") (name "unconnected-(U4-NC-Pad2)") (class "Default")
      (node (ref "U4") (pin "2") (pinfunction "NC_2") (pintype "passive"))
    )
    (net (code "208") (name "unconnected-(U4-NC-Pad3)") (class "Default")
      (node (ref "U4") (pin "3") (pinfunction "NC_3") (pintype "passive"))
    )
    (net (code "209") (name "unconnected-(U4-NC-Pad4)") (class "Default")
      (node (ref "U4") (pin "4") (pinfunction "NC_4") (pintype "passive"))
    )
    (net (code "210") (name "unconnected-(U4-NC-Pad5)") (class "Default")
      (node (ref "U4") (pin "5") (pinfunction "NC_5") (pintype "passive"))
    )
    (net (code "211") (name "unconnected-(U4-NC-Pad6)") (class "Default")
      (node (ref "U4") (pin "6") (pinfunction "NC_6") (pintype "passive"))
    )
    (net (code "212") (name "unconnected-(U4-NC-Pad14)") (class "Default")
      (node (ref "U4") (pin "14") (pinfunction "NC_14") (pintype "passive"))
    )
    (net (code "213") (name "unconnected-(U4-NC-Pad15)") (class "Default")
      (node (ref "U4") (pin "15") (pinfunction "NC_15") (pintype "passive"))
    )
    (net (code "214") (name "unconnected-(U4-NC-Pad16)") (class "Default")
      (node (ref "U4") (pin "16") (pinfunction "NC_16") (pintype "passive"))
    )
    (net (code "215") (name "unconnected-(U4-NC-Pad17)") (class "Default")
      (node (ref "U4") (pin "17") (pinfunction "NC_17") (pintype "passive"))
    )
    (net (code "216") (name "unconnected-(U4-RESV-Pad19)") (class "Default")
      (node (ref "U4") (pin "19") (pinfunction "RESV_19") (pintype "passive"))
    )
    (net (code "217") (name "unconnected-(U5-DRDY-Pad15)") (class "Default")
      (node (ref "U5") (pin "15") (pinfunction "DRDY_15") (pintype "passive"))
    )
    (net (code "218") (name "unconnected-(U5-NC-Pad3)") (class "Default")
      (node (ref "U5") (pin "3") (pinfunction "NC_3") (pintype "passive"))
    )
    (net (code "219") (name "unconnected-(U5-NC-Pad5)") (class "Default")
      (node (ref "U5") (pin "5") (pinfunction "NC_5") (pintype "passive"))
    )
    (net (code "220") (name "unconnected-(U5-NC-Pad6)") (class "Default")
      (node (ref "U5") (pin "6") (pinfunction "NC_6") (pintype "passive"))
    )
    (net (code "221") (name "unconnected-(U5-NC-Pad7)") (class "Default")
      (node (ref "U5") (pin "7") (pinfunction "NC_7") (pintype "passive"))
    )
    (net (code "222") (name "unconnected-(U5-NC-Pad14)") (class "Default")
      (node (ref "U5") (pin "14") (pinfunction "NC_14") (pintype "passive"))
    )
    (net (code "223") (name "unconnected-(U9-DEN-Pad8)") (class "Default")
      (node (ref "U9") (pin "8") (pinfunction "DEN_8") (pintype "passive"))
    )
    (net (code "224") (name "unconnected-(U9-INT1-Pad7)") (class "Default")
      (node (ref "U9") (pin "7") (pinfunction "INT1_7") (pintype "passive"))
    )
    (net (code "225") (name "unconnected-(USB1-ID-Pad4)") (class "Default")
      (node (ref "USB1") (pin "4") (pinfunction "ID_4") (pintype "passive"))
    )
    (net (code "226") (name "unconnected-(USB2-ID-Pad4)") (class "Default")
      (node (ref "USB2") (pin "4") (pinfunction "ID_4") (pintype "passive"))
    )
  )
)
